# BLDC.net
KiCad netlist of a schematic drawn in EasyEDA Pro
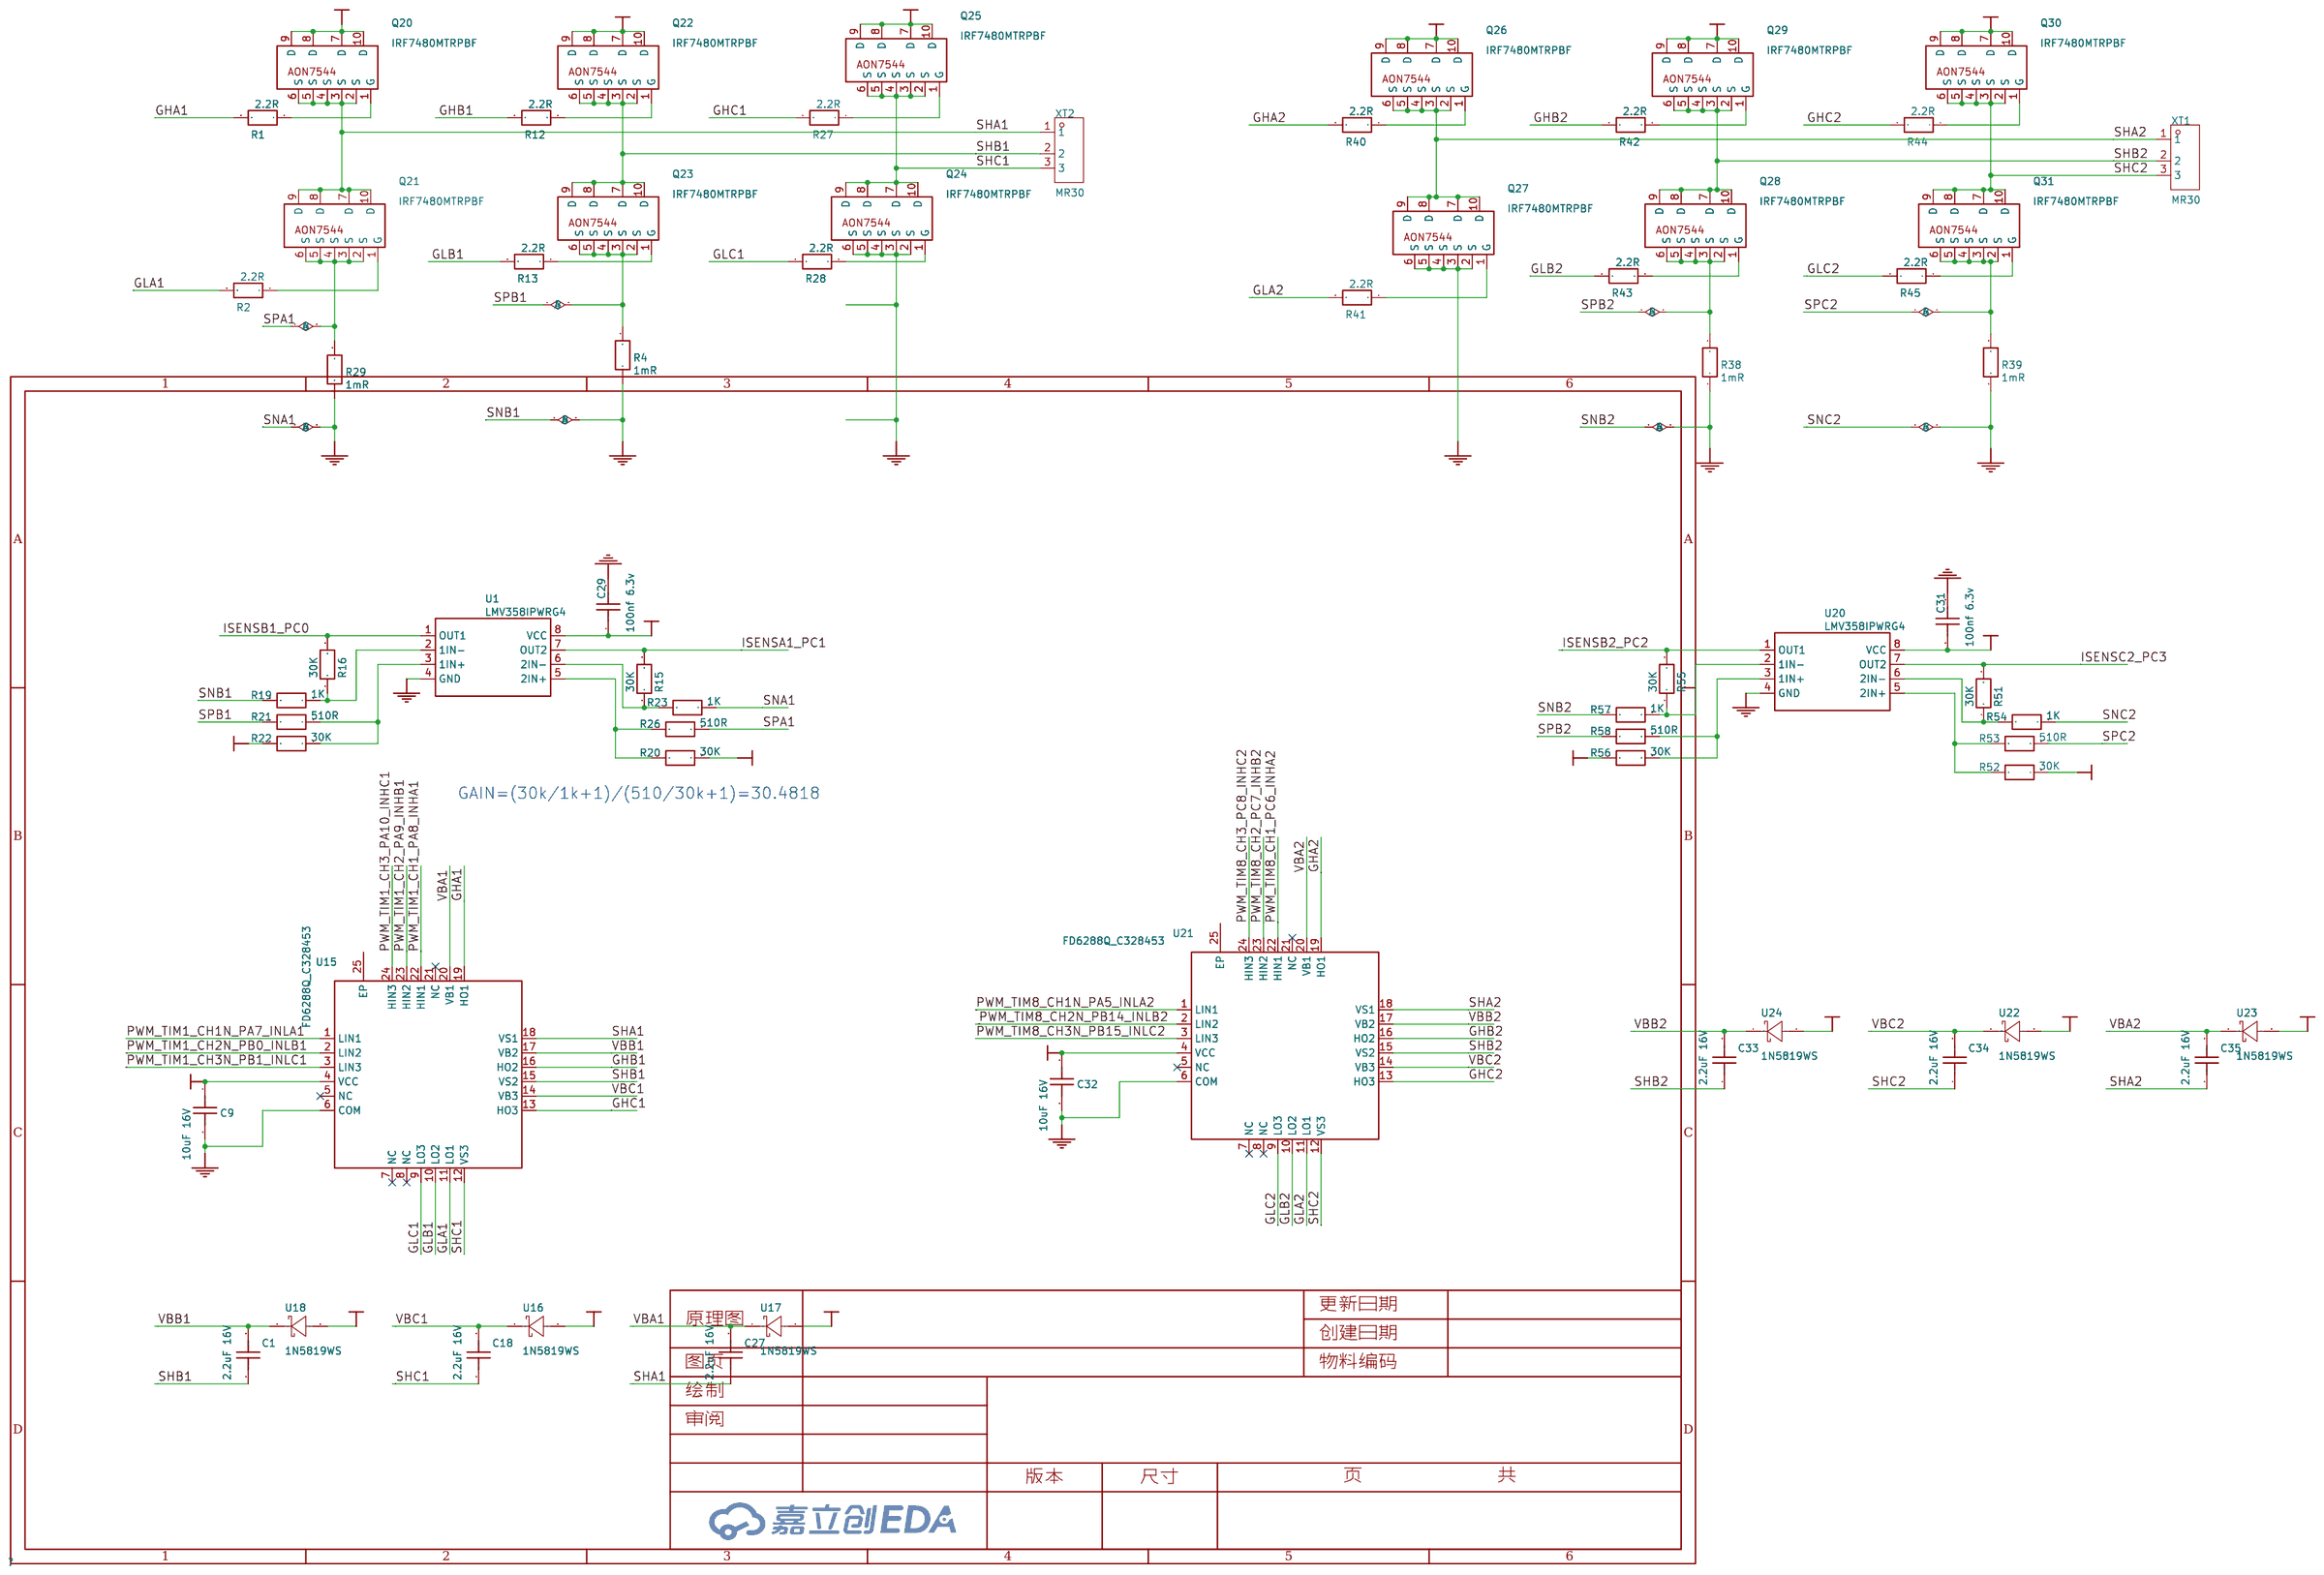
[diagram p0: 驱动]
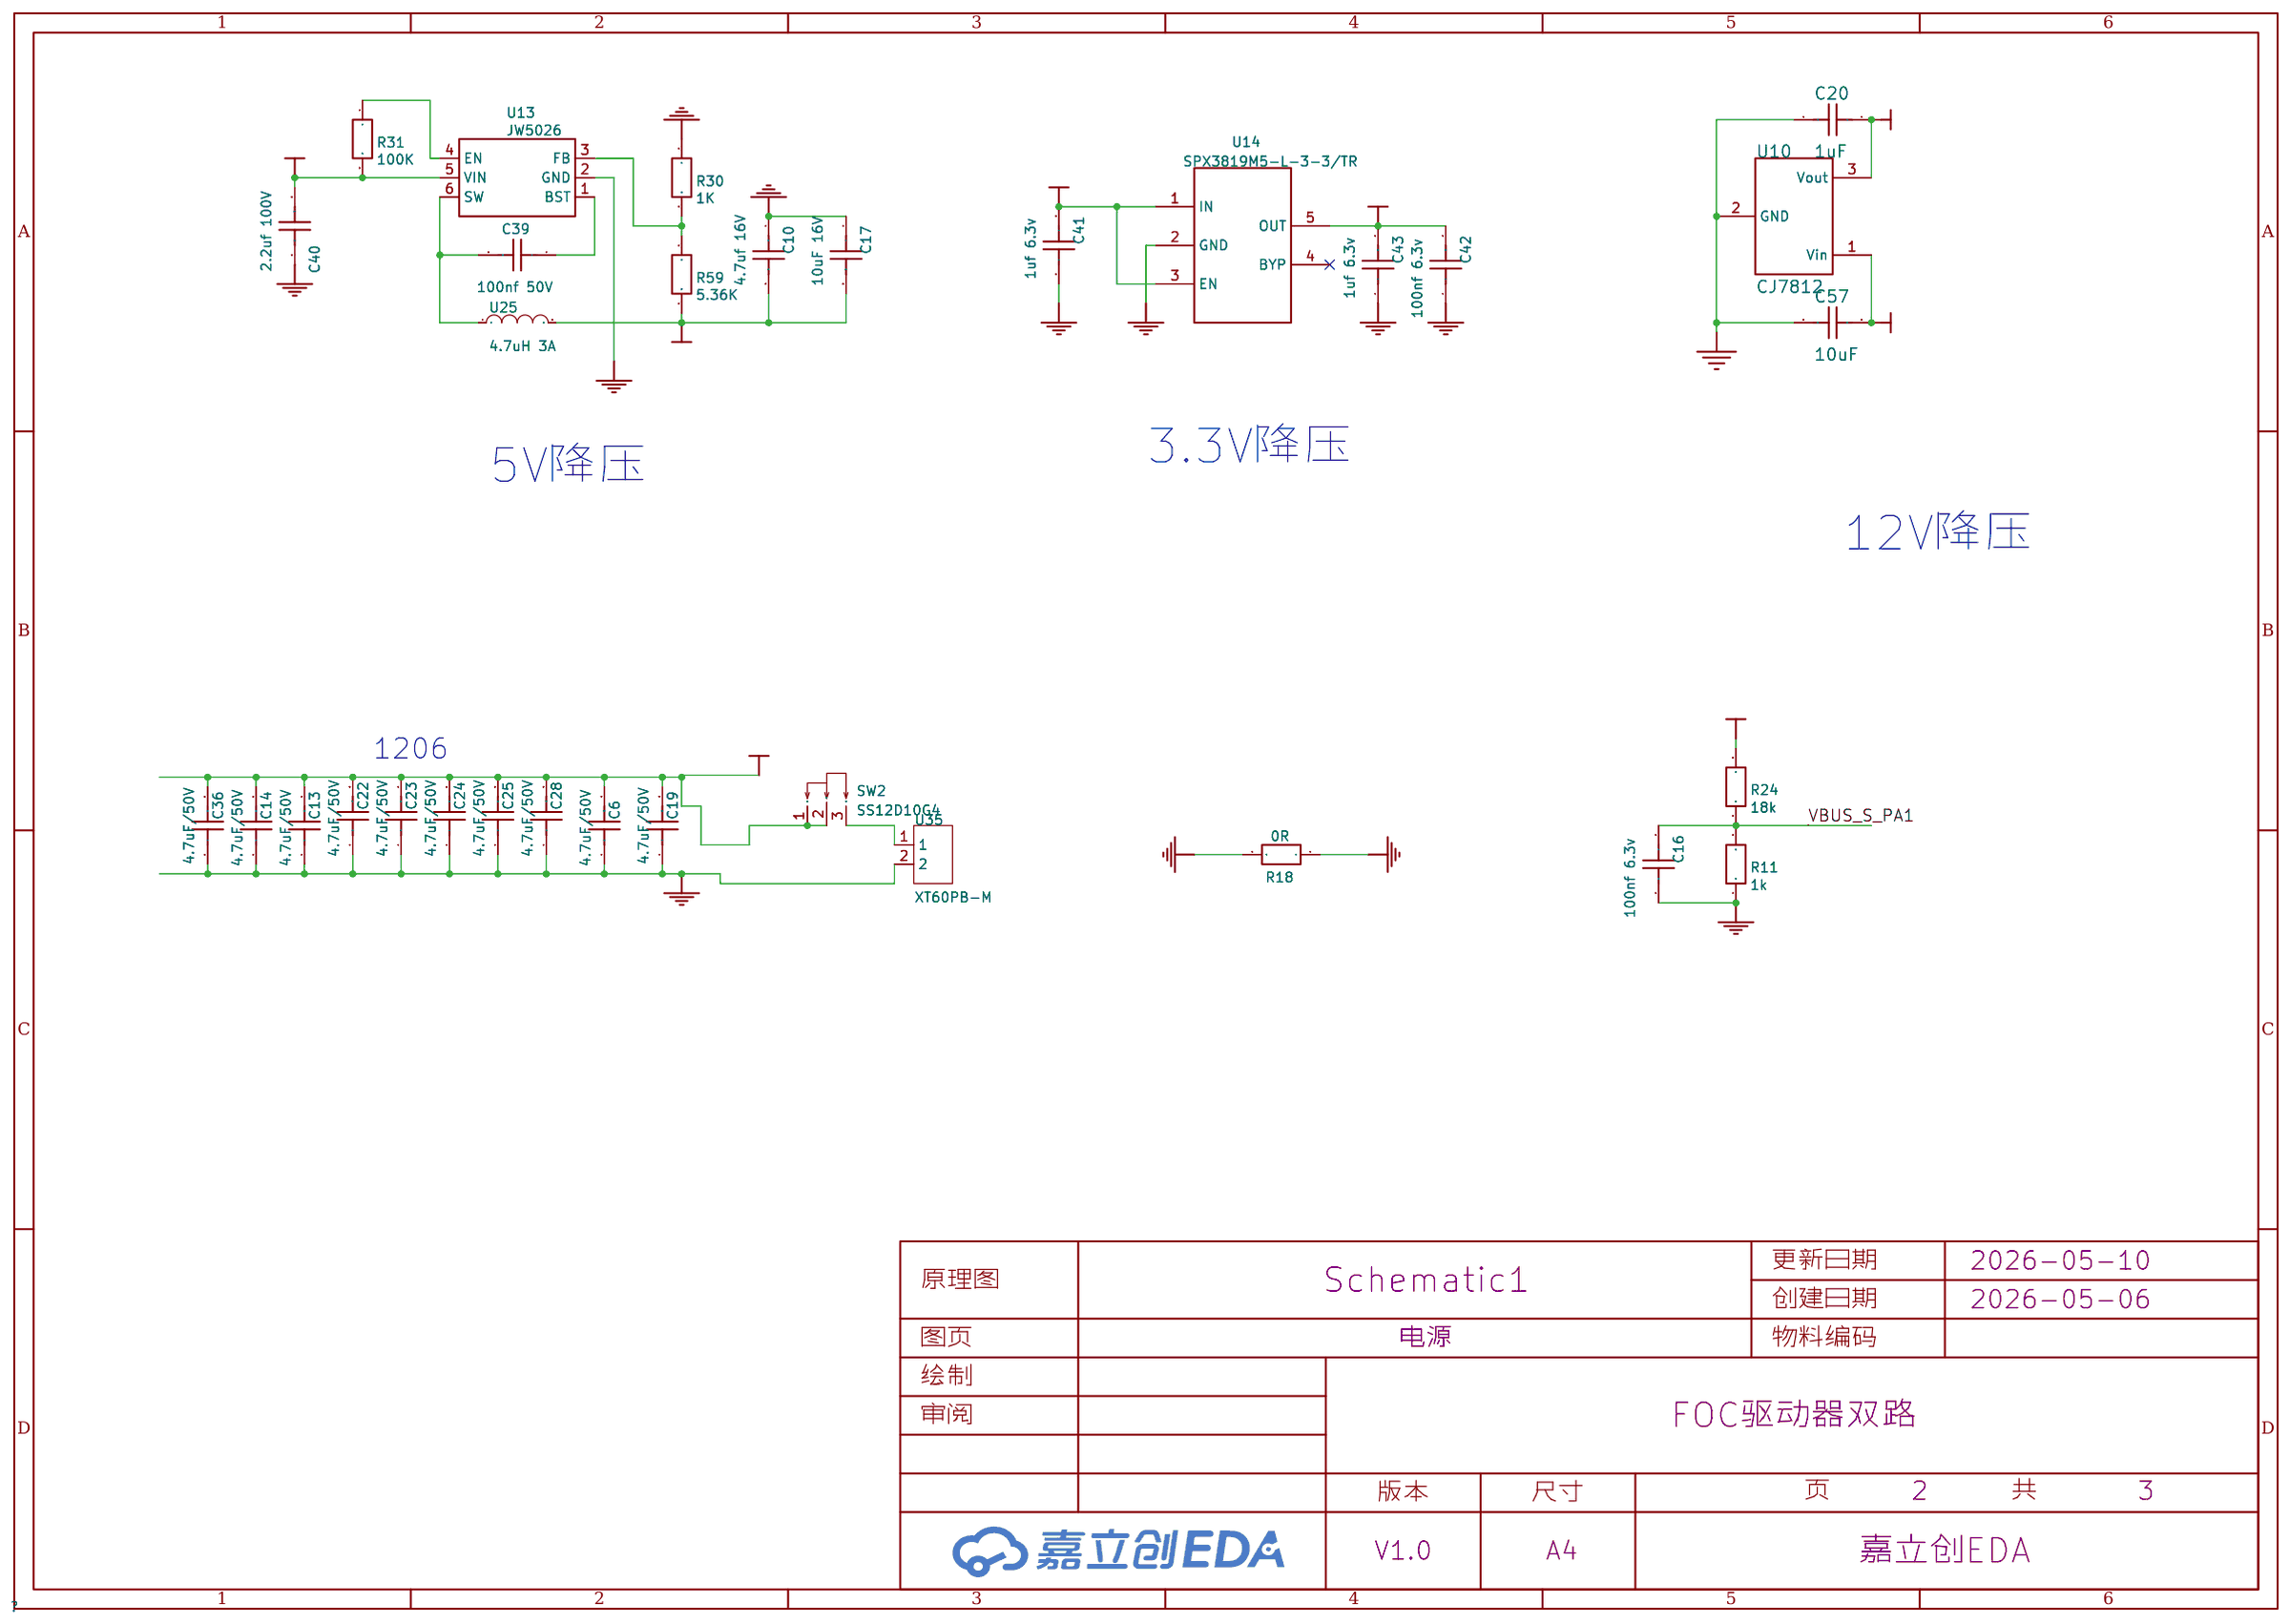
[diagram p1: 电源]
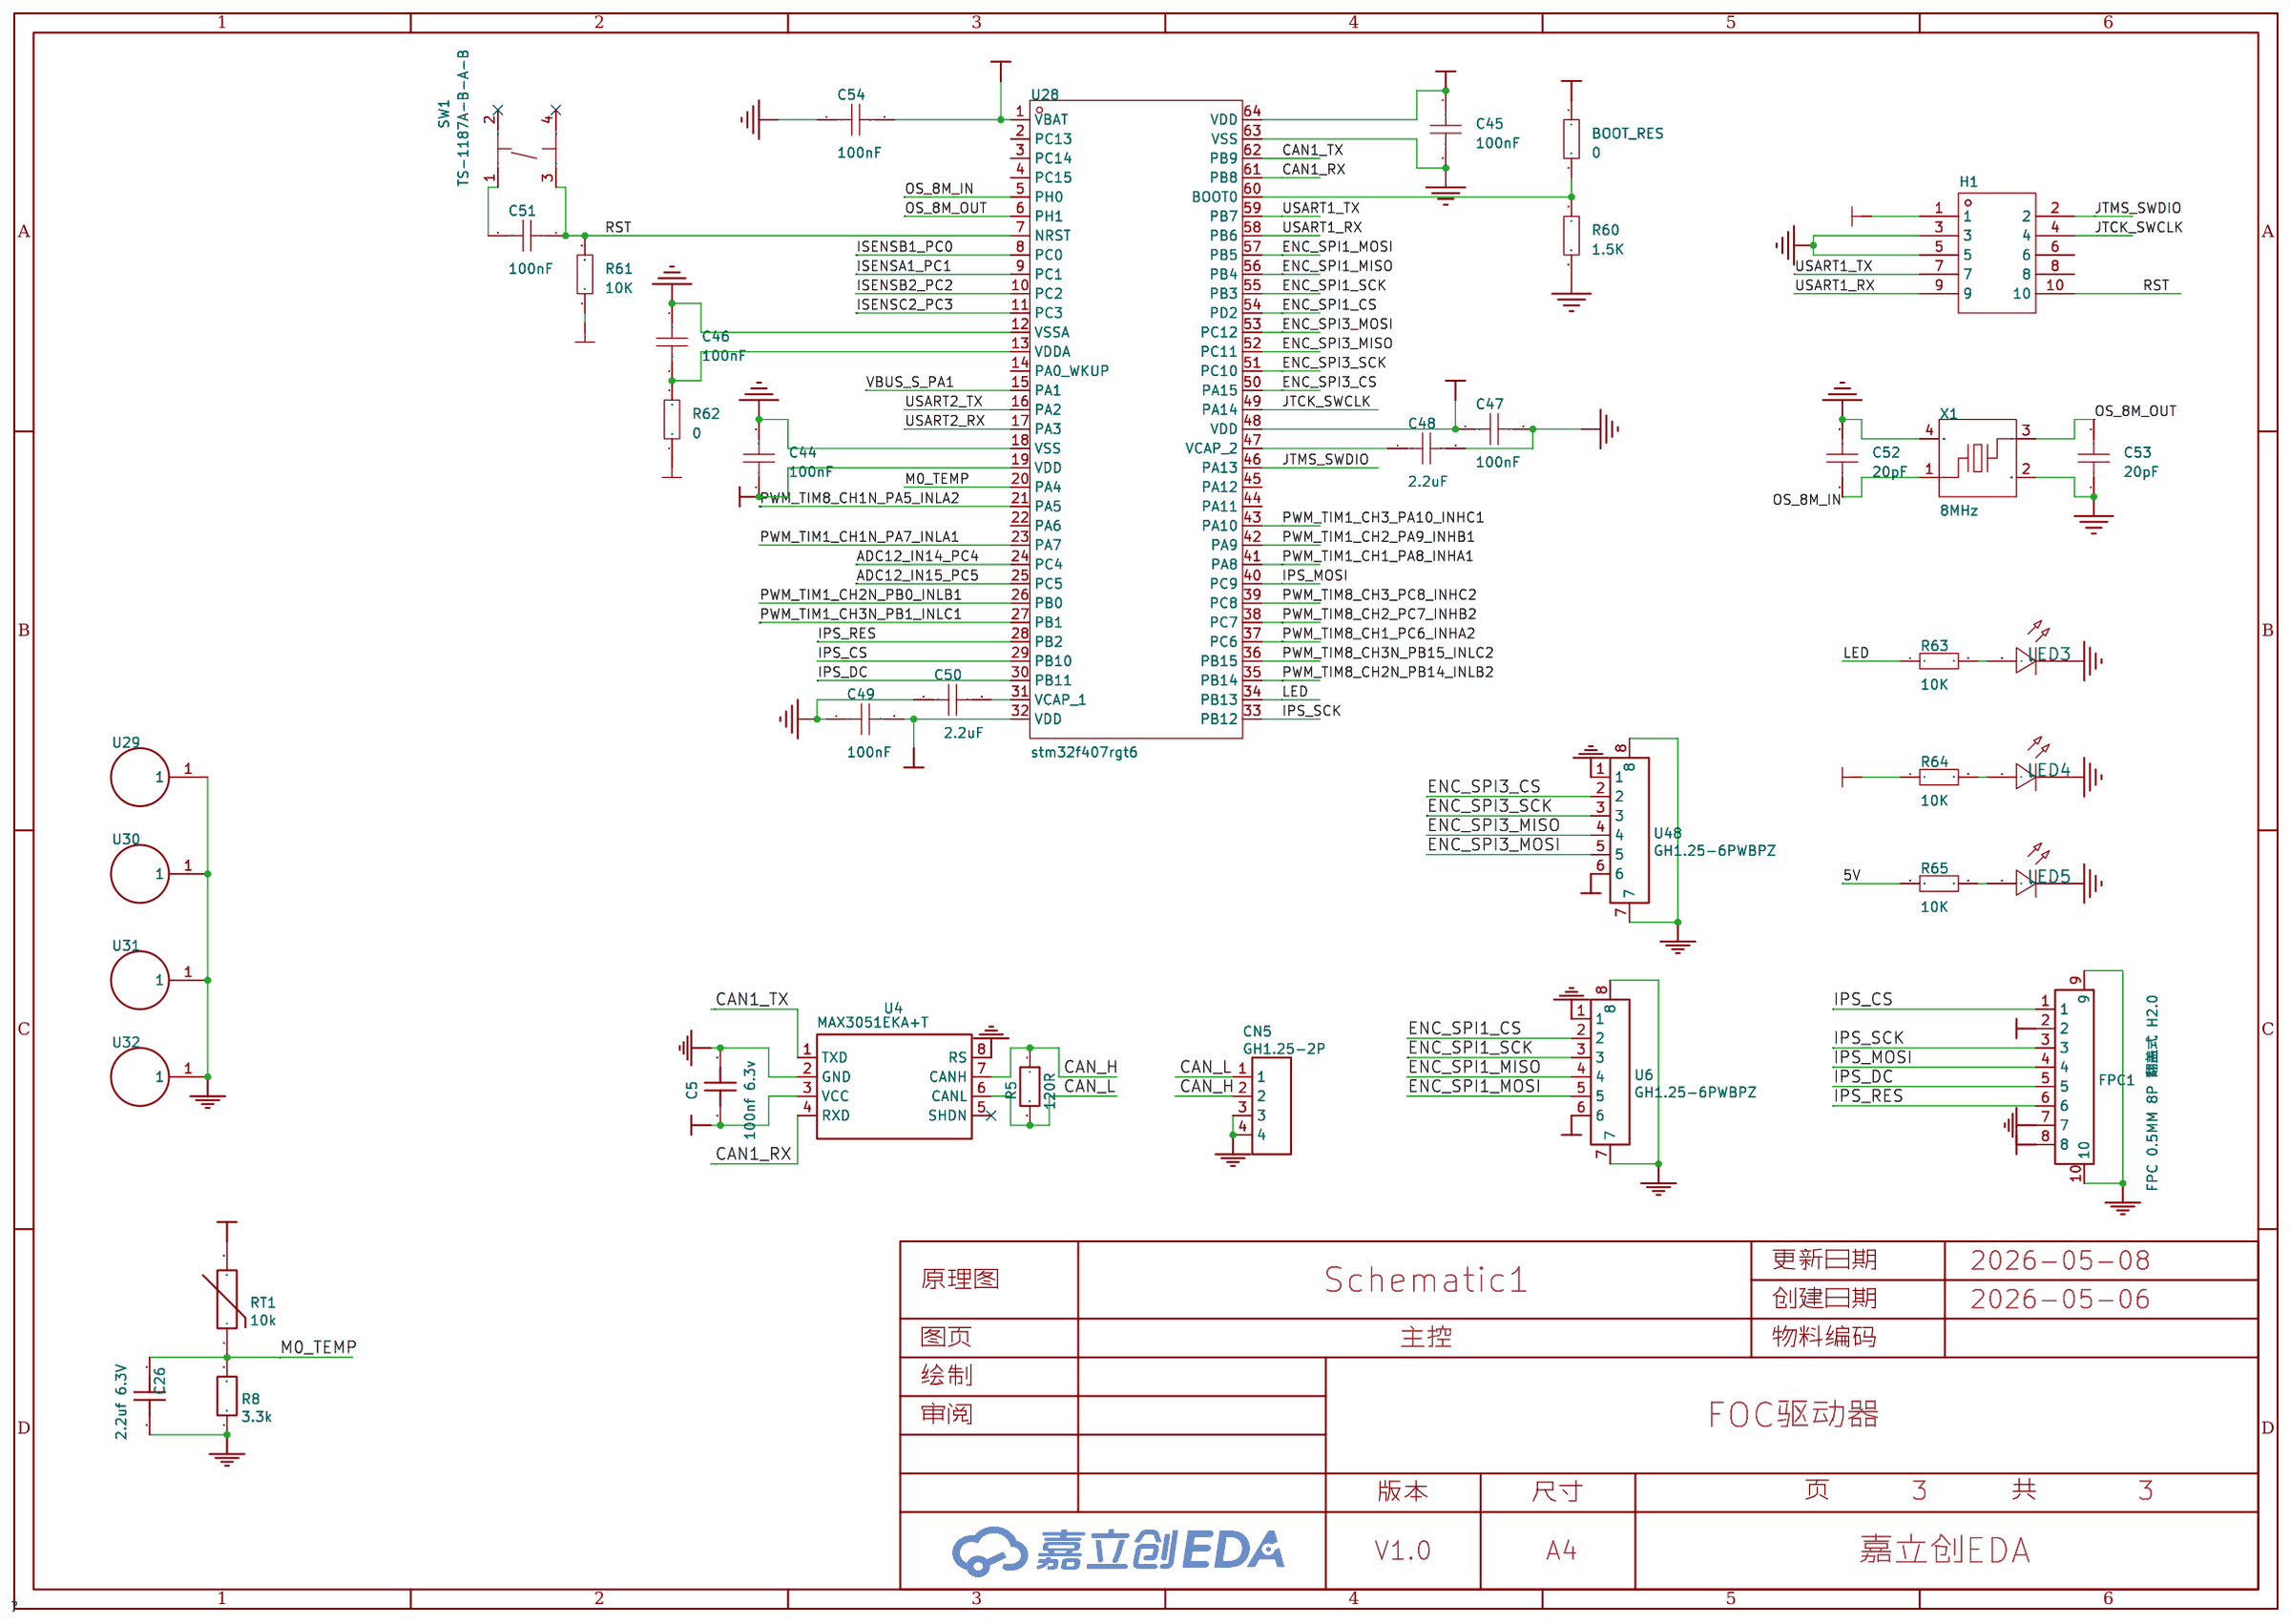
[diagram p2: 主控]

(export (version "E")
  (design (tool "Eeschema 10.0.6"))
  (components
    (comp (ref "C1")
      (value "2.2uF 16V")
      (footprint "easyedapro:C0603")
      (fields (field (name "Contributor") "LCEDA_Lib"))
      (libsource (lib "easyedapro") (part "2.2uF 16V"))
    )
    (comp (ref "C9")
      (value "10uF 16V")
      (footprint "easyedapro:C0805")
      (fields (field (name "Contributor") "LCEDA_Lib"))
      (libsource (lib "easyedapro") (part "10uF 16V"))
    )
    (comp (ref "C18")
      (value "2.2uF 16V")
      (footprint "easyedapro:C0603")
      (fields (field (name "Contributor") "LCEDA_Lib"))
      (libsource (lib "easyedapro") (part "2.2uF 16V"))
    )
    (comp (ref "C27")
      (value "2.2uF 16V")
      (footprint "easyedapro:C0603")
      (fields (field (name "Contributor") "LCEDA_Lib"))
      (libsource (lib "easyedapro") (part "2.2uF 16V"))
    )
    (comp (ref "C29")
      (value "100nf 6.3v")
      (footprint "easyedapro:C0603")
      (fields (field (name "Contributor") "LCEDA_Lib"))
      (libsource (lib "easyedapro") (part "100nf 6.3v"))
    )
    (comp (ref "C31")
      (value "100nf 6.3v")
      (footprint "easyedapro:C0603")
      (fields (field (name "Contributor") "LCEDA_Lib"))
      (libsource (lib "easyedapro") (part "100nf 6.3v"))
    )
    (comp (ref "C32")
      (value "10uF 16V")
      (footprint "easyedapro:C0805")
      (fields (field (name "Contributor") "LCEDA_Lib"))
      (libsource (lib "easyedapro") (part "10uF 16V"))
    )
    (comp (ref "C33")
      (value "2.2uF 16V")
      (footprint "easyedapro:C0603")
      (fields (field (name "Contributor") "LCEDA_Lib"))
      (libsource (lib "easyedapro") (part "2.2uF 16V"))
    )
    (comp (ref "C34")
      (value "2.2uF 16V")
      (footprint "easyedapro:C0603")
      (fields (field (name "Contributor") "LCEDA_Lib"))
      (libsource (lib "easyedapro") (part "2.2uF 16V"))
    )
    (comp (ref "C35")
      (value "2.2uF 16V")
      (footprint "easyedapro:C0603")
      (fields (field (name "Contributor") "LCEDA_Lib"))
      (libsource (lib "easyedapro") (part "2.2uF 16V"))
    )
    (comp (ref "Q20")
      (value "IRF7480MTRPBF")
      (footprint "easyedapro:TRS-SMD_IRF7480MTRPBF")
      (fields (field (name "Manufacturer") "Infineon(英飞凌)"))
      (libsource (lib "easyedapro") (part "IRF7480MTRPBF"))
    )
    (comp (ref "Q21")
      (value "IRF7480MTRPBF")
      (footprint "easyedapro:TRS-SMD_IRF7480MTRPBF")
      (fields (field (name "Manufacturer") "Infineon(英飞凌)"))
      (libsource (lib "easyedapro") (part "IRF7480MTRPBF"))
    )
    (comp (ref "Q22")
      (value "IRF7480MTRPBF")
      (footprint "easyedapro:TRS-SMD_IRF7480MTRPBF")
      (fields (field (name "Manufacturer") "Infineon(英飞凌)"))
      (libsource (lib "easyedapro") (part "IRF7480MTRPBF"))
    )
    (comp (ref "Q23")
      (value "IRF7480MTRPBF")
      (footprint "easyedapro:TRS-SMD_IRF7480MTRPBF")
      (fields (field (name "Manufacturer") "Infineon(英飞凌)"))
      (libsource (lib "easyedapro") (part "IRF7480MTRPBF"))
    )
    (comp (ref "Q24")
      (value "IRF7480MTRPBF")
      (footprint "easyedapro:TRS-SMD_IRF7480MTRPBF")
      (fields (field (name "Manufacturer") "Infineon(英飞凌)"))
      (libsource (lib "easyedapro") (part "IRF7480MTRPBF"))
    )
    (comp (ref "Q25")
      (value "IRF7480MTRPBF")
      (footprint "easyedapro:TRS-SMD_IRF7480MTRPBF")
      (fields (field (name "Manufacturer") "Infineon(英飞凌)"))
      (libsource (lib "easyedapro") (part "IRF7480MTRPBF"))
    )
    (comp (ref "Q26")
      (value "IRF7480MTRPBF")
      (footprint "easyedapro:TRS-SMD_IRF7480MTRPBF")
      (fields (field (name "Manufacturer") "Infineon(英飞凌)"))
      (libsource (lib "easyedapro") (part "IRF7480MTRPBF"))
    )
    (comp (ref "Q27")
      (value "IRF7480MTRPBF")
      (footprint "easyedapro:TRS-SMD_IRF7480MTRPBF")
      (fields (field (name "Manufacturer") "Infineon(英飞凌)"))
      (libsource (lib "easyedapro") (part "IRF7480MTRPBF"))
    )
    (comp (ref "Q28")
      (value "IRF7480MTRPBF")
      (footprint "easyedapro:TRS-SMD_IRF7480MTRPBF")
      (fields (field (name "Manufacturer") "Infineon(英飞凌)"))
      (libsource (lib "easyedapro") (part "IRF7480MTRPBF"))
    )
    (comp (ref "Q29")
      (value "IRF7480MTRPBF")
      (footprint "easyedapro:TRS-SMD_IRF7480MTRPBF")
      (fields (field (name "Manufacturer") "Infineon(英飞凌)"))
      (libsource (lib "easyedapro") (part "IRF7480MTRPBF"))
    )
    (comp (ref "Q30")
      (value "IRF7480MTRPBF")
      (footprint "easyedapro:TRS-SMD_IRF7480MTRPBF")
      (fields (field (name "Manufacturer") "Infineon(英飞凌)"))
      (libsource (lib "easyedapro") (part "IRF7480MTRPBF"))
    )
    (comp (ref "Q31")
      (value "IRF7480MTRPBF")
      (footprint "easyedapro:TRS-SMD_IRF7480MTRPBF")
      (fields (field (name "Manufacturer") "Infineon(英飞凌)"))
      (libsource (lib "easyedapro") (part "IRF7480MTRPBF"))
    )
    (comp (ref "R1")
      (value "2.2R")
      (footprint "easyedapro:R0603")
      (fields (field (name "Contributor") "LCEDA_Lib"))
      (libsource (lib "easyedapro") (part "2.2R"))
    )
    (comp (ref "R2")
      (value "2.2R")
      (footprint "easyedapro:R0603")
      (fields (field (name "Contributor") "LCEDA_Lib"))
      (libsource (lib "easyedapro") (part "2.2R"))
    )
    (comp (ref "R4")
      (value "1mR")
      (footprint "easyedapro:R1206")
      (fields (field (name "Contributor") "LCEDA_Lib"))
      (libsource (lib "easyedapro") (part "1mR"))
    )
    (comp (ref "R12")
      (value "2.2R")
      (footprint "easyedapro:R0603")
      (fields (field (name "Contributor") "LCEDA_Lib"))
      (libsource (lib "easyedapro") (part "2.2R"))
    )
    (comp (ref "R13")
      (value "2.2R")
      (footprint "easyedapro:R0603")
      (fields (field (name "Contributor") "LCEDA_Lib"))
      (libsource (lib "easyedapro") (part "2.2R"))
    )
    (comp (ref "R15")
      (value "30K")
      (footprint "easyedapro:R0603")
      (fields (field (name "Contributor") "LCEDA_Lib"))
      (libsource (lib "") (part "30K_1"))
    )
    (comp (ref "R16")
      (value "30K")
      (footprint "easyedapro:R0603")
      (fields (field (name "Contributor") "LCEDA_Lib"))
      (libsource (lib "") (part "30K_1"))
    )
    (comp (ref "R19")
      (value "1K")
      (footprint "easyedapro:R0603")
      (fields (field (name "Contributor") "LCEDA_Lib"))
      (libsource (lib "easyedapro") (part "1K"))
    )
    (comp (ref "R20")
      (value "30K")
      (footprint "easyedapro:R0603")
      (fields (field (name "Contributor") "LCEDA_Lib"))
      (libsource (lib "easyedapro") (part "30K"))
    )
    (comp (ref "R21")
      (value "510R")
      (footprint "easyedapro:R0603")
      (fields (field (name "Contributor") "LCEDA_Lib"))
      (libsource (lib "easyedapro") (part "510R"))
    )
    (comp (ref "R22")
      (value "30K")
      (footprint "easyedapro:R0603")
      (fields (field (name "Contributor") "LCEDA_Lib"))
      (libsource (lib "easyedapro") (part "30K"))
    )
    (comp (ref "R23")
      (value "1K")
      (footprint "easyedapro:R0603")
      (fields (field (name "Contributor") "LCEDA_Lib"))
      (libsource (lib "easyedapro") (part "1K"))
    )
    (comp (ref "R26")
      (value "510R")
      (footprint "easyedapro:R0603")
      (fields (field (name "Contributor") "LCEDA_Lib"))
      (libsource (lib "easyedapro") (part "510R"))
    )
    (comp (ref "R27")
      (value "2.2R")
      (footprint "easyedapro:R0603")
      (fields (field (name "Contributor") "LCEDA_Lib"))
      (libsource (lib "easyedapro") (part "2.2R"))
    )
    (comp (ref "R28")
      (value "2.2R")
      (footprint "easyedapro:R0603")
      (fields (field (name "Contributor") "LCEDA_Lib"))
      (libsource (lib "easyedapro") (part "2.2R"))
    )
    (comp (ref "R29")
      (value "1mR")
      (footprint "easyedapro:R1206")
      (fields (field (name "Contributor") "LCEDA_Lib"))
      (libsource (lib "easyedapro") (part "1mR"))
    )
    (comp (ref "R38")
      (value "1mR")
      (footprint "easyedapro:R1206")
      (fields (field (name "Contributor") "LCEDA_Lib"))
      (libsource (lib "easyedapro") (part "1mR"))
    )
    (comp (ref "R39")
      (value "1mR")
      (footprint "easyedapro:R1206")
      (fields (field (name "Contributor") "LCEDA_Lib"))
      (libsource (lib "easyedapro") (part "1mR"))
    )
    (comp (ref "R40")
      (value "2.2R")
      (footprint "easyedapro:R0603")
      (fields (field (name "Contributor") "LCEDA_Lib"))
      (libsource (lib "easyedapro") (part "2.2R"))
    )
    (comp (ref "R41")
      (value "2.2R")
      (footprint "easyedapro:R0603")
      (fields (field (name "Contributor") "LCEDA_Lib"))
      (libsource (lib "easyedapro") (part "2.2R"))
    )
    (comp (ref "R42")
      (value "2.2R")
      (footprint "easyedapro:R0603")
      (fields (field (name "Contributor") "LCEDA_Lib"))
      (libsource (lib "easyedapro") (part "2.2R"))
    )
    (comp (ref "R43")
      (value "2.2R")
      (footprint "easyedapro:R0603")
      (fields (field (name "Contributor") "LCEDA_Lib"))
      (libsource (lib "easyedapro") (part "2.2R"))
    )
    (comp (ref "R44")
      (value "2.2R")
      (footprint "easyedapro:R0603")
      (fields (field (name "Contributor") "LCEDA_Lib"))
      (libsource (lib "easyedapro") (part "2.2R"))
    )
    (comp (ref "R45")
      (value "2.2R")
      (footprint "easyedapro:R0603")
      (fields (field (name "Contributor") "LCEDA_Lib"))
      (libsource (lib "easyedapro") (part "2.2R"))
    )
    (comp (ref "R51")
      (value "30K")
      (footprint "easyedapro:R0603")
      (fields (field (name "Contributor") "LCEDA_Lib"))
      (libsource (lib "") (part "30K_1"))
    )
    (comp (ref "R52")
      (value "30K")
      (footprint "easyedapro:R0603")
      (fields (field (name "Contributor") "LCEDA_Lib"))
      (libsource (lib "easyedapro") (part "30K"))
    )
    (comp (ref "R53")
      (value "510R")
      (footprint "easyedapro:R0603")
      (fields (field (name "Contributor") "LCEDA_Lib"))
      (libsource (lib "easyedapro") (part "510R"))
    )
    (comp (ref "R54")
      (value "1K")
      (footprint "easyedapro:R0603")
      (fields (field (name "Contributor") "LCEDA_Lib"))
      (libsource (lib "easyedapro") (part "1K"))
    )
    (comp (ref "R55")
      (value "30K")
      (footprint "easyedapro:R0603")
      (fields (field (name "Contributor") "LCEDA_Lib"))
      (libsource (lib "") (part "30K_1"))
    )
    (comp (ref "R56")
      (value "30K")
      (footprint "easyedapro:R0603")
      (fields (field (name "Contributor") "LCEDA_Lib"))
      (libsource (lib "easyedapro") (part "30K"))
    )
    (comp (ref "R57")
      (value "1K")
      (footprint "easyedapro:R0603")
      (fields (field (name "Contributor") "LCEDA_Lib"))
      (libsource (lib "easyedapro") (part "1K"))
    )
    (comp (ref "R58")
      (value "510R")
      (footprint "easyedapro:R0603")
      (fields (field (name "Contributor") "LCEDA_Lib"))
      (libsource (lib "easyedapro") (part "510R"))
    )
    (comp (ref "U1")
      (value "LMV358IPWRG4")
      (footprint "easyedapro:TSSOP-8_L4.4-W3.0-P0.65-LS6.4-BL")
      (fields (field (name "Manufacturer") "TI"))
      (libsource (lib "easyedapro") (part "LMV358IPWRG4"))
    )
    (comp (ref "U15")
      (value "FD6288Q_C328453")
      (footprint "easyedapro:QFN-24_L4.0-W4.0-P0.50-BL-EP2.6")
      (fields
        (field (name "Manufacturer Part") "FD6288Q")
        (field (name "Manufacturer") "Fortior Tech")
        (field (name "Contributor") "LCSC")
      )
      (libsource (lib "easyedapro") (part "FD6288Q_C328453"))
    )
    (comp (ref "U16")
      (value "1N5819WS")
      (footprint "easyedapro:SOD-323_L1.7-W1.3-LS2.6-RD")
      (description "正向压降(Vf):600mV@1A;直流反向耐压(Vr):40V;整流电流:1A;")
      (fields (field (name "Manufacturer") "TECH PUBLIC(台舟)"))
      (libsource (lib "easyedapro") (part "1N5819WS_C7202959"))
    )
    (comp (ref "U17")
      (value "1N5819WS")
      (footprint "easyedapro:SOD-323_L1.7-W1.3-LS2.6-RD")
      (description "正向压降(Vf):600mV@1A;直流反向耐压(Vr):40V;整流电流:1A;")
      (fields (field (name "Manufacturer") "TECH PUBLIC(台舟)"))
      (libsource (lib "easyedapro") (part "1N5819WS_C7202959"))
    )
    (comp (ref "U18")
      (value "1N5819WS")
      (footprint "easyedapro:SOD-323_L1.7-W1.3-LS2.6-RD")
      (description "正向压降(Vf):600mV@1A;直流反向耐压(Vr):40V;整流电流:1A;")
      (fields (field (name "Manufacturer") "TECH PUBLIC(台舟)"))
      (libsource (lib "easyedapro") (part "1N5819WS_C7202959"))
    )
    (comp (ref "U20")
      (value "LMV358IPWRG4")
      (footprint "easyedapro:TSSOP-8_L4.4-W3.0-P0.65-LS6.4-BL")
      (fields (field (name "Manufacturer") "TI"))
      (libsource (lib "easyedapro") (part "LMV358IPWRG4"))
    )
    (comp (ref "U21")
      (value "FD6288Q_C328453")
      (footprint "easyedapro:QFN-24_L4.0-W4.0-P0.50-BL-EP2.6")
      (fields
        (field (name "Manufacturer Part") "FD6288Q")
        (field (name "Manufacturer") "Fortior Tech")
        (field (name "Contributor") "LCSC")
      )
      (libsource (lib "easyedapro") (part "FD6288Q_C328453"))
    )
    (comp (ref "U22")
      (value "1N5819WS")
      (footprint "easyedapro:SOD-323_L1.7-W1.3-LS2.6-RD")
      (description "正向压降(Vf):600mV@1A;直流反向耐压(Vr):40V;整流电流:1A;")
      (fields (field (name "Manufacturer") "TECH PUBLIC(台舟)"))
      (libsource (lib "easyedapro") (part "1N5819WS_C7202959"))
    )
    (comp (ref "U23")
      (value "1N5819WS")
      (footprint "easyedapro:SOD-323_L1.7-W1.3-LS2.6-RD")
      (description "正向压降(Vf):600mV@1A;直流反向耐压(Vr):40V;整流电流:1A;")
      (fields (field (name "Manufacturer") "TECH PUBLIC(台舟)"))
      (libsource (lib "easyedapro") (part "1N5819WS_C7202959"))
    )
    (comp (ref "U24")
      (value "1N5819WS")
      (footprint "easyedapro:SOD-323_L1.7-W1.3-LS2.6-RD")
      (description "正向压降(Vf):600mV@1A;直流反向耐压(Vr):40V;整流电流:1A;")
      (fields (field (name "Manufacturer") "TECH PUBLIC(台舟)"))
      (libsource (lib "easyedapro") (part "1N5819WS_C7202959"))
    )
    (comp (ref "U38")
      (value "~")
      (footprint "easyedapro:网络连接")
      (description "不同网络明间连接")
      (libsource (lib "easyedapro") (part "网络链接"))
    )
    (comp (ref "U39")
      (value "~")
      (footprint "easyedapro:网络连接")
      (description "不同网络明间连接")
      (libsource (lib "easyedapro") (part "网络链接"))
    )
    (comp (ref "U40")
      (value "~")
      (footprint "easyedapro:网络连接")
      (description "不同网络明间连接")
      (libsource (lib "easyedapro") (part "网络链接"))
    )
    (comp (ref "U41")
      (value "~")
      (footprint "easyedapro:网络连接")
      (description "不同网络明间连接")
      (libsource (lib "easyedapro") (part "网络链接"))
    )
    (comp (ref "U44")
      (value "~")
      (footprint "easyedapro:网络连接")
      (description "不同网络明间连接")
      (libsource (lib "easyedapro") (part "网络链接"))
    )
    (comp (ref "U45")
      (value "~")
      (footprint "easyedapro:网络连接")
      (description "不同网络明间连接")
      (libsource (lib "easyedapro") (part "网络链接"))
    )
    (comp (ref "U46")
      (value "~")
      (footprint "easyedapro:网络连接")
      (description "不同网络明间连接")
      (libsource (lib "easyedapro") (part "网络链接"))
    )
    (comp (ref "U47")
      (value "~")
      (footprint "easyedapro:网络连接")
      (description "不同网络明间连接")
      (libsource (lib "easyedapro") (part "网络链接"))
    )
    (comp (ref "XT1")
      (value "MR30")
      (footprint "easyedapro:CONN-TH_MR30PB-M")
      (libsource (lib "easyedapro") (part "MR30"))
    )
    (comp (ref "XT2")
      (value "MR30")
      (footprint "easyedapro:CONN-TH_MR30PB-M")
      (libsource (lib "easyedapro") (part "MR30"))
    )
    (comp (ref "C6")
      (value "4.7uF/50V")
      (footprint "easyedapro:C1206")
      (fields (field (name "Contributor") "LCEDA_Lib"))
      (libsource (lib "easyedapro") (part "4.7uF/50V"))
    )
    (comp (ref "C10")
      (value "4.7uf 16V")
      (footprint "easyedapro:C0603")
      (fields (field (name "Contributor") "LCEDA_Lib"))
      (libsource (lib "easyedapro") (part "4.7uf 16V"))
    )
    (comp (ref "C13")
      (value "4.7uF/50V")
      (footprint "easyedapro:C1206")
      (fields (field (name "Contributor") "LCEDA_Lib"))
      (libsource (lib "easyedapro") (part "4.7uF/50V"))
    )
    (comp (ref "C14")
      (value "4.7uF/50V")
      (footprint "easyedapro:C1206")
      (fields (field (name "Contributor") "LCEDA_Lib"))
      (libsource (lib "easyedapro") (part "4.7uF/50V"))
    )
    (comp (ref "C16")
      (value "100nf 6.3v")
      (footprint "easyedapro:C0603")
      (fields (field (name "Contributor") "LCEDA_Lib"))
      (libsource (lib "easyedapro") (part "100nf 6.3v"))
    )
    (comp (ref "C17")
      (value "10uF 16V")
      (footprint "easyedapro:C0805")
      (fields (field (name "Contributor") "LCEDA_Lib"))
      (libsource (lib "easyedapro") (part "10uF 16V"))
    )
    (comp (ref "C19")
      (value "4.7uF/50V")
      (footprint "easyedapro:C1206")
      (fields (field (name "Contributor") "LCEDA_Lib"))
      (libsource (lib "easyedapro") (part "4.7uF/50V"))
    )
    (comp (ref "C20")
      (value "1uF")
      (footprint "easyedapro:C0603")
      (libsource (lib "easyedapro") (part "CapAcitance"))
    )
    (comp (ref "C22")
      (value "4.7uF/50V")
      (footprint "easyedapro:C1206")
      (fields (field (name "Contributor") "LCEDA_Lib"))
      (libsource (lib "easyedapro") (part "4.7uF/50V"))
    )
    (comp (ref "C23")
      (value "4.7uF/50V")
      (footprint "easyedapro:C1206")
      (fields (field (name "Contributor") "LCEDA_Lib"))
      (libsource (lib "easyedapro") (part "4.7uF/50V"))
    )
    (comp (ref "C24")
      (value "4.7uF/50V")
      (footprint "easyedapro:C1206")
      (fields (field (name "Contributor") "LCEDA_Lib"))
      (libsource (lib "easyedapro") (part "4.7uF/50V"))
    )
    (comp (ref "C25")
      (value "4.7uF/50V")
      (footprint "easyedapro:C1206")
      (fields (field (name "Contributor") "LCEDA_Lib"))
      (libsource (lib "easyedapro") (part "4.7uF/50V"))
    )
    (comp (ref "C28")
      (value "4.7uF/50V")
      (footprint "easyedapro:C1206")
      (fields (field (name "Contributor") "LCEDA_Lib"))
      (libsource (lib "easyedapro") (part "4.7uF/50V"))
    )
    (comp (ref "C36")
      (value "4.7uF/50V")
      (footprint "easyedapro:C1206")
      (fields (field (name "Contributor") "LCEDA_Lib"))
      (libsource (lib "easyedapro") (part "4.7uF/50V"))
    )
    (comp (ref "C39")
      (value "100nf 50V")
      (footprint "easyedapro:C0603")
      (fields (field (name "Contributor") "LCEDA_Lib"))
      (libsource (lib "easyedapro") (part "100nf 50V"))
    )
    (comp (ref "C40")
      (value "2.2uf 100V")
      (footprint "easyedapro:C0805")
      (fields (field (name "Contributor") "LCEDA_Lib"))
      (libsource (lib "easyedapro") (part "2.2uf 100V"))
    )
    (comp (ref "C41")
      (value "1uf 6.3v")
      (footprint "easyedapro:C0603")
      (fields (field (name "Contributor") "LCEDA_Lib"))
      (libsource (lib "easyedapro") (part "1uf 6.3v"))
    )
    (comp (ref "C42")
      (value "100nf 6.3v")
      (footprint "easyedapro:C0603")
      (fields (field (name "Contributor") "LCEDA_Lib"))
      (libsource (lib "easyedapro") (part "100nf 6.3v"))
    )
    (comp (ref "C43")
      (value "1uf 6.3v")
      (footprint "easyedapro:C0603")
      (fields (field (name "Contributor") "LCEDA_Lib"))
      (libsource (lib "easyedapro") (part "1uf 6.3v"))
    )
    (comp (ref "C57")
      (value "10uF")
      (footprint "easyedapro:C0603")
      (libsource (lib "easyedapro") (part "CapAcitance"))
    )
    (comp (ref "R11")
      (value "1k")
      (footprint "easyedapro:R0603")
      (fields (field (name "Contributor") "LCEDA_Lib"))
      (libsource (lib "easyedapro") (part "1k"))
    )
    (comp (ref "R18")
      (value "0R")
      (footprint "easyedapro:R0603")
      (fields (field (name "Contributor") "LCEDA_Lib"))
      (libsource (lib "easyedapro") (part "0R"))
    )
    (comp (ref "R24")
      (value "18k")
      (footprint "easyedapro:R0603")
      (fields (field (name "Contributor") "LCEDA_Lib"))
      (libsource (lib "easyedapro") (part "18k"))
    )
    (comp (ref "R30")
      (value "1K")
      (footprint "easyedapro:R0603")
      (fields (field (name "Contributor") "LCEDA_Lib"))
      (libsource (lib "easyedapro") (part "1K"))
    )
    (comp (ref "R31")
      (value "100K")
      (footprint "easyedapro:R0603")
      (fields (field (name "Contributor") "LCEDA_Lib"))
      (libsource (lib "easyedapro") (part "100K"))
    )
    (comp (ref "R59")
      (value "5.36K")
      (footprint "easyedapro:R0603")
      (fields (field (name "Contributor") "LCEDA_Lib"))
      (libsource (lib "easyedapro") (part "5.36K"))
    )
    (comp (ref "SW2")
      (value "SS12D10G4")
      (footprint "easyedapro:SW-TH_3P-P4.80-HX-SS12D10G4")
      (fields (field (name "Manufacturer") "HanElectricity(瀚源)"))
      (libsource (lib "easyedapro") (part "SS12D10G4"))
    )
    (comp (ref "U10")
      (value "CJ7812")
      (footprint "easyedapro:TO-252-3_L6.5-W5.8-P4.58-BL")
      (fields (field (name "Manufacturer") "CJ(江苏长电/长晶)"))
      (libsource (lib "easyedapro") (part "CJ7812 3%"))
    )
    (comp (ref "U13")
      (value "JW5026")
      (footprint "easyedapro:SOT-23-6_L2.9-W1.6-P0.95-LS2.8-BR")
      (fields (field (name "Manufacturer") "JoulWatt Tech") (field (name "Contributor") "LCSC"))
      (libsource (lib "easyedapro") (part "JW5026"))
    )
    (comp (ref "U14")
      (value "SPX3819M5-L-3-3/TR")
      (footprint "easyedapro:SOT-23-5_L3.0-W1.7-P0.95-LS2.8-BR")
      (fields (field (name "Manufacturer") "EXAR"))
      (libsource (lib "easyedapro") (part "SPX3819M5-L-3-3/TR"))
    )
    (comp (ref "U25")
      (value "4.7uH 3A")
      (footprint "easyedapro:IND-SMD_L7.3-W7.3_GSDRH74P")
      (libsource (lib "easyedapro") (part "4.7UH 3A"))
    )
    (comp (ref "U35")
      (value "XT60PB-M")
      (footprint "easyedapro:CONN-TH_XT60PB-M")
      (libsource (lib "easyedapro") (part "XT60PB-M"))
    )
    (comp (ref "BOOT_RES")
      (value "0")
      (footprint "easyedapro:R0603")
      (libsource (lib "easyedapro") (part "电阻"))
    )
    (comp (ref "C5")
      (value "100nf 6.3v")
      (footprint "easyedapro:C0603")
      (fields (field (name "Contributor") "LCEDA_Lib"))
      (libsource (lib "easyedapro") (part "100nf 6.3v"))
    )
    (comp (ref "C26")
      (value "2.2uf 6.3V")
      (footprint "easyedapro:C0603")
      (fields (field (name "Contributor") "LCEDA_Lib"))
      (libsource (lib "easyedapro") (part "2.2uf 6.3V"))
    )
    (comp (ref "C44")
      (value "100nF")
      (footprint "easyedapro:C0603")
      (libsource (lib "easyedapro") (part "Capacitance"))
    )
    (comp (ref "C45")
      (value "100nF")
      (footprint "easyedapro:C0603")
      (libsource (lib "easyedapro") (part "Capacitance"))
    )
    (comp (ref "C46")
      (value "100nF")
      (footprint "easyedapro:C0603")
      (libsource (lib "easyedapro") (part "Capacitance"))
    )
    (comp (ref "C47")
      (value "100nF")
      (footprint "easyedapro:C0603")
      (libsource (lib "easyedapro") (part "Capacitance"))
    )
    (comp (ref "C48")
      (value "2.2uF")
      (footprint "easyedapro:C0603")
      (libsource (lib "easyedapro") (part "Capacitance"))
    )
    (comp (ref "C49")
      (value "100nF")
      (footprint "easyedapro:C0603")
      (libsource (lib "easyedapro") (part "Capacitance"))
    )
    (comp (ref "C50")
      (value "2.2uF")
      (footprint "easyedapro:C0603")
      (libsource (lib "easyedapro") (part "Capacitance"))
    )
    (comp (ref "C51")
      (value "100nF")
      (footprint "easyedapro:C0603")
      (libsource (lib "easyedapro") (part "Capacitance"))
    )
    (comp (ref "C52")
      (value "20pF")
      (footprint "easyedapro:C0603")
      (libsource (lib "easyedapro") (part "Capacitance"))
    )
    (comp (ref "C53")
      (value "20pF")
      (footprint "easyedapro:C0603")
      (libsource (lib "easyedapro") (part "Capacitance"))
    )
    (comp (ref "C54")
      (value "100nF")
      (footprint "easyedapro:C0603")
      (libsource (lib "easyedapro") (part "Capacitance"))
    )
    (comp (ref "CN5")
      (value "GH1.25-2P")
      (footprint "easyedapro:CONN-SMD_2P-P1.25_GH1.25-2P")
      (fields (field (name "Contributor") "LCSC"))
      (libsource (lib "easyedapro") (part "GH1.25-2P"))
    )
    (comp (ref "FPC1")
      (value "FPC 0.5MM 8P 翻盖式 H2.0")
      (footprint "easyedapro:FPC-SMD_FPC-0.5MM-8P")
      (fields (field (name "Manufacturer") "ATOM(爱特姆)") (field (name "Contributor") "LCSC"))
      (libsource (lib "easyedapro") (part "FPC 0.5MM 8P 翻盖式 H2.0"))
    )
    (comp (ref "H1")
      (value "~")
      (footprint "easyedapro:HDR-TH_10P-P2.54-V-M-R2-C5-S2.54")
      (libsource (lib "easyedapro") (part "HDR-M-2.54_2x5"))
    )
    (comp (ref "LED3")
      (value "~")
      (footprint "easyedapro:LED_0603")
      (libsource (lib "easyedapro") (part "LED_R"))
    )
    (comp (ref "LED4")
      (value "~")
      (footprint "easyedapro:LED_0603")
      (libsource (lib "easyedapro") (part "LED_R"))
    )
    (comp (ref "LED5")
      (value "~")
      (footprint "easyedapro:LED_0603")
      (libsource (lib "easyedapro") (part "LED_R"))
    )
    (comp (ref "R5")
      (value "120R")
      (footprint "easyedapro:R0603")
      (fields (field (name "Contributor") "LCEDA_Lib"))
      (libsource (lib "easyedapro") (part "120R"))
    )
    (comp (ref "R8")
      (value "3.3k")
      (footprint "easyedapro:R0603")
      (fields (field (name "Contributor") "LCEDA_Lib"))
      (libsource (lib "easyedapro") (part "3.3k"))
    )
    (comp (ref "R60")
      (value "1.5K")
      (footprint "easyedapro:R0603")
      (libsource (lib "easyedapro") (part "电阻"))
    )
    (comp (ref "R61") (value "10K") (footprint "easyedapro:R0603") (libsource (lib "easyedapro") (part "电阻")))
    (comp (ref "R62") (value "0") (footprint "easyedapro:R0603") (libsource (lib "easyedapro") (part "电阻")))
    (comp (ref "R63") (value "10K") (footprint "easyedapro:R0603") (libsource (lib "easyedapro") (part "电阻")))
    (comp (ref "R64") (value "10K") (footprint "easyedapro:R0603") (libsource (lib "easyedapro") (part "电阻")))
    (comp (ref "R65") (value "10K") (footprint "easyedapro:R0603") (libsource (lib "easyedapro") (part "电阻")))
    (comp (ref "RT1")
      (value "10k")
      (footprint "easyedapro:R0603")
      (fields
        (field (name "Manufacturer Part") "NTCG164BH103JT1")
        (field (name "Manufacturer") "TDK")
        (field (name "Contributor") "LCSC")
      )
      (libsource (lib "easyedapro") (part "10k"))
    )
    (comp (ref "SW1")
      (value "TS-1187A-B-A-B")
      (footprint "easyedapro:SW-SMD_4P-L5.1-W5.1-P3.70-LS6.5-TL_H1.5")
      (fields (field (name "Manufacturer") "XKB Connection(中国星坤)"))
      (libsource (lib "easyedapro") (part "TS-1187A-B-A-B"))
    )
    (comp (ref "U4")
      (value "MAX3051EKA+T")
      (footprint "easyedapro:SOT-23-8_L3.0-W1.7-P0.65-LS2.8-TL")
      (fields (field (name "Manufacturer") "MAXIM"))
      (libsource (lib "easyedapro") (part "MAX3051EKA+T"))
    )
    (comp (ref "U6")
      (value "GH1.25-6PWBPZ")
      (footprint "easyedapro:CONN-SMD_6P-P1.25_GH1.25-6PWBPZ")
      (fields (field (name "Manufacturer") "BOOMELE(博穆精密)") (field (name "Contributor") "LCSC"))
      (libsource (lib "easyedapro") (part "GH1.25-6PWBPZ"))
    )
    (comp (ref "U28")
      (value "stm32f407rgt6")
      (footprint "easyedapro:LQFP-64_L10.0-W10.0-P0.50-LS12.0-BL")
      (libsource (lib "easyedapro") (part "STM32F407RGT6"))
    )
    (comp (ref "U29")
      (value "~")
      (footprint "easyedapro:M3")
      (description "M3定位孔")
      (libsource (lib "easyedapro") (part "M3"))
    )
    (comp (ref "U30")
      (value "~")
      (footprint "easyedapro:M3")
      (description "M3定位孔")
      (libsource (lib "easyedapro") (part "M3"))
    )
    (comp (ref "U31")
      (value "~")
      (footprint "easyedapro:M3")
      (description "M3定位孔")
      (libsource (lib "easyedapro") (part "M3"))
    )
    (comp (ref "U32")
      (value "~")
      (footprint "easyedapro:M3")
      (description "M3定位孔")
      (libsource (lib "easyedapro") (part "M3"))
    )
    (comp (ref "U48")
      (value "GH1.25-6PWBPZ")
      (footprint "easyedapro:CONN-SMD_6P-P1.25_GH1.25-6PWBPZ")
      (fields (field (name "Manufacturer") "BOOMELE(博穆精密)") (field (name "Contributor") "LCSC"))
      (libsource (lib "easyedapro") (part "GH1.25-6PWBPZ"))
    )
    (comp (ref "X1")
      (value "8MHz")
      (footprint "easyedapro:CRYSTAL-SMD_4P-L3.2-W2.5-BL-1")
      (description "晶振类型:贴片晶振;频率:8MHz;常温频差:±10ppm;负载电容:12pF;频率稳定度:±20ppm;")
      (fields
        (field (name "Manufacturer Part") "XL2EL89COI-111YLC-8M")
        (field (name "Manufacturer") "YXC(扬兴晶振)")
      )
      (libsource (lib "easyedapro") (part "XL2EL89COI-111YLC-8M"))
    )
  )
  (nets
    (net (code "1") (name "5V") (class "Default")
      (node (ref "C10") (pin "2") (pinfunction "2_2") (pintype "unspecified"))
      (node (ref "C17") (pin "2") (pinfunction "2_2") (pintype "unspecified"))
      (node (ref "C41") (pin "2") (pinfunction "2_2") (pintype "unspecified"))
      (node (ref "R59") (pin "2") (pinfunction "2_2") (pintype "unspecified"))
      (node (ref "R65") (pin "1") (pinfunction "1_1") (pintype "input"))
      (node (ref "U14") (pin "1") (pinfunction "IN_1") (pintype "unspecified"))
      (node (ref "U14") (pin "3") (pinfunction "EN_3") (pintype "unspecified"))
      (node (ref "U25") (pin "2") (pinfunction "2_2") (pintype "unspecified"))
    )
    (net (code "2") (name "12V") (class "Default")
      (node (ref "C20") (pin "1") (pinfunction "1_1") (pintype "input"))
      (node (ref "C32") (pin "1") (pinfunction "1_1") (pintype "unspecified"))
      (node (ref "C9") (pin "1") (pinfunction "1_1") (pintype "unspecified"))
      (node (ref "U10") (pin "3") (pinfunction "Vout_3") (pintype "unspecified"))
      (node (ref "U15") (pin "4") (pinfunction "VCC_4") (pintype "unspecified"))
      (node (ref "U16") (pin "2") (pinfunction "A_2") (pintype "unspecified"))
      (node (ref "U17") (pin "2") (pinfunction "A_2") (pintype "unspecified"))
      (node (ref "U18") (pin "2") (pinfunction "A_2") (pintype "unspecified"))
      (node (ref "U21") (pin "4") (pinfunction "VCC_4") (pintype "unspecified"))
      (node (ref "U22") (pin "2") (pinfunction "A_2") (pintype "unspecified"))
      (node (ref "U23") (pin "2") (pinfunction "A_2") (pintype "unspecified"))
      (node (ref "U24") (pin "2") (pinfunction "A_2") (pintype "unspecified"))
    )
    (net (code "3") (name "ADC12_IN14_PC4") (class "Default")
      (node (ref "U28") (pin "24") (pinfunction "PC4_24") (pintype "unspecified"))
    )
    (net (code "4") (name "ADC12_IN15_PC5") (class "Default")
      (node (ref "U28") (pin "25") (pinfunction "PC5_25") (pintype "unspecified"))
    )
    (net (code "5") (name "CAN1_RX") (class "Default")
      (node (ref "U28") (pin "61") (pinfunction "PB8_61") (pintype "unspecified"))
      (node (ref "U4") (pin "4") (pinfunction "RXD_4") (pintype "unspecified"))
    )
    (net (code "6") (name "CAN1_TX") (class "Default")
      (node (ref "U28") (pin "62") (pinfunction "PB9_62") (pintype "unspecified"))
      (node (ref "U4") (pin "1") (pinfunction "TXD_1") (pintype "unspecified"))
    )
    (net (code "7") (name "CAN_H") (class "Default")
      (node (ref "CN5") (pin "2") (pinfunction "2_2") (pintype "unspecified"))
      (node (ref "R5") (pin "1") (pinfunction "1_1") (pintype "unspecified"))
      (node (ref "U4") (pin "7") (pinfunction "CANH_7") (pintype "unspecified"))
    )
    (net (code "8") (name "CAN_L") (class "Default")
      (node (ref "CN5") (pin "1") (pinfunction "1_1") (pintype "unspecified"))
      (node (ref "R5") (pin "2") (pinfunction "2_2") (pintype "unspecified"))
      (node (ref "U4") (pin "6") (pinfunction "CANL_6") (pintype "unspecified"))
    )
    (net (code "9") (name "DCBUS") (class "Default")
      (node (ref "C13") (pin "2") (pinfunction "2_2") (pintype "unspecified"))
      (node (ref "C14") (pin "2") (pinfunction "2_2") (pintype "unspecified"))
      (node (ref "C19") (pin "2") (pinfunction "2_2") (pintype "unspecified"))
      (node (ref "C22") (pin "2") (pinfunction "2_2") (pintype "unspecified"))
      (node (ref "C23") (pin "2") (pinfunction "2_2") (pintype "unspecified"))
      (node (ref "C24") (pin "2") (pinfunction "2_2") (pintype "unspecified"))
      (node (ref "C25") (pin "2") (pinfunction "2_2") (pintype "unspecified"))
      (node (ref "C28") (pin "2") (pinfunction "2_2") (pintype "unspecified"))
      (node (ref "C36") (pin "2") (pinfunction "2_2") (pintype "unspecified"))
      (node (ref "C40") (pin "2") (pinfunction "2_2") (pintype "unspecified"))
      (node (ref "C57") (pin "1") (pinfunction "1_1") (pintype "input"))
      (node (ref "C6") (pin "2") (pinfunction "2_2") (pintype "unspecified"))
      (node (ref "Q20") (pin "10") (pinfunction "D_10") (pintype "unspecified"))
      (node (ref "Q20") (pin "7") (pinfunction "D_7") (pintype "unspecified"))
      (node (ref "Q20") (pin "8") (pinfunction "D_8") (pintype "unspecified"))
      (node (ref "Q20") (pin "9") (pinfunction "D_9") (pintype "unspecified"))
      (node (ref "Q22") (pin "10") (pinfunction "D_10") (pintype "unspecified"))
      (node (ref "Q22") (pin "7") (pinfunction "D_7") (pintype "unspecified"))
      (node (ref "Q22") (pin "8") (pinfunction "D_8") (pintype "unspecified"))
      (node (ref "Q22") (pin "9") (pinfunction "D_9") (pintype "unspecified"))
      (node (ref "Q25") (pin "10") (pinfunction "D_10") (pintype "unspecified"))
      (node (ref "Q25") (pin "7") (pinfunction "D_7") (pintype "unspecified"))
      (node (ref "Q25") (pin "8") (pinfunction "D_8") (pintype "unspecified"))
      (node (ref "Q25") (pin "9") (pinfunction "D_9") (pintype "unspecified"))
      (node (ref "Q26") (pin "10") (pinfunction "D_10") (pintype "unspecified"))
      (node (ref "Q26") (pin "7") (pinfunction "D_7") (pintype "unspecified"))
      (node (ref "Q26") (pin "8") (pinfunction "D_8") (pintype "unspecified"))
      (node (ref "Q26") (pin "9") (pinfunction "D_9") (pintype "unspecified"))
      (node (ref "Q29") (pin "10") (pinfunction "D_10") (pintype "unspecified"))
      (node (ref "Q29") (pin "7") (pinfunction "D_7") (pintype "unspecified"))
      (node (ref "Q29") (pin "8") (pinfunction "D_8") (pintype "unspecified"))
      (node (ref "Q29") (pin "9") (pinfunction "D_9") (pintype "unspecified"))
      (node (ref "Q30") (pin "10") (pinfunction "D_10") (pintype "unspecified"))
      (node (ref "Q30") (pin "7") (pinfunction "D_7") (pintype "unspecified"))
      (node (ref "Q30") (pin "8") (pinfunction "D_8") (pintype "unspecified"))
      (node (ref "Q30") (pin "9") (pinfunction "D_9") (pintype "unspecified"))
      (node (ref "R24") (pin "2") (pinfunction "2_2") (pintype "unspecified"))
      (node (ref "R31") (pin "2") (pinfunction "2_2") (pintype "unspecified"))
      (node (ref "SW2") (pin "1") (pinfunction "1_1") (pintype "unspecified"))
      (node (ref "SW2") (pin "2") (pinfunction "2_2") (pintype "unspecified"))
      (node (ref "U10") (pin "1") (pinfunction "Vin_1") (pintype "unspecified"))
      (node (ref "U13") (pin "5") (pinfunction "VIN_5") (pintype "unspecified"))
    )
    (net (code "10") (name "DGND") (class "Default")
      (node (ref "C10") (pin "1") (pinfunction "1_1") (pintype "unspecified"))
      (node (ref "C16") (pin "1") (pinfunction "1_1") (pintype "unspecified"))
      (node (ref "C17") (pin "1") (pinfunction "1_1") (pintype "unspecified"))
      (node (ref "C20") (pin "2") (pinfunction "2_2") (pintype "input"))
      (node (ref "C26") (pin "2") (pinfunction "2_2") (pintype "unspecified"))
      (node (ref "C29") (pin "2") (pinfunction "2_2") (pintype "unspecified"))
      (node (ref "C31") (pin "2") (pinfunction "2_2") (pintype "unspecified"))
      (node (ref "C32") (pin "2") (pinfunction "2_2") (pintype "unspecified"))
      (node (ref "C40") (pin "1") (pinfunction "1_1") (pintype "unspecified"))
      (node (ref "C41") (pin "1") (pinfunction "1_1") (pintype "unspecified"))
      (node (ref "C42") (pin "1") (pinfunction "1_1") (pintype "unspecified"))
      (node (ref "C43") (pin "1") (pinfunction "1_1") (pintype "unspecified"))
      (node (ref "C44") (pin "2") (pinfunction "2_2") (pintype "input"))
      (node (ref "C45") (pin "2") (pinfunction "2_2") (pintype "input"))
      (node (ref "C46") (pin "2") (pinfunction "2_2") (pintype "input"))
      (node (ref "C47") (pin "2") (pinfunction "2_2") (pintype "input"))
      (node (ref "C48") (pin "2") (pinfunction "2_2") (pintype "input"))
      (node (ref "C49") (pin "1") (pinfunction "1_1") (pintype "input"))
      (node (ref "C5") (pin "2") (pinfunction "2_2") (pintype "unspecified"))
      (node (ref "C50") (pin "1") (pinfunction "1_1") (pintype "input"))
      (node (ref "C52") (pin "2") (pinfunction "2_2") (pintype "input"))
      (node (ref "C53") (pin "1") (pinfunction "1_1") (pintype "input"))
      (node (ref "C54") (pin "1") (pinfunction "1_1") (pintype "input"))
      (node (ref "C57") (pin "2") (pinfunction "2_2") (pintype "input"))
      (node (ref "C9") (pin "2") (pinfunction "2_2") (pintype "unspecified"))
      (node (ref "CN5") (pin "3") (pinfunction "3_3") (pintype "unspecified"))
      (node (ref "CN5") (pin "4") (pinfunction "4_4") (pintype "unspecified"))
      (node (ref "FPC1") (pin "10") (pinfunction "10_10") (pintype "unspecified"))
      (node (ref "FPC1") (pin "7") (pinfunction "7_7") (pintype "unspecified"))
      (node (ref "FPC1") (pin "9") (pinfunction "9_9") (pintype "unspecified"))
      (node (ref "H1") (pin "3") (pinfunction "3_3") (pintype "input"))
      (node (ref "H1") (pin "5") (pinfunction "5_5") (pintype "input"))
      (node (ref "LED3") (pin "1") (pinfunction "C_1") (pintype "input"))
      (node (ref "LED4") (pin "1") (pinfunction "C_1") (pintype "input"))
      (node (ref "LED5") (pin "1") (pinfunction "C_1") (pintype "input"))
      (node (ref "R11") (pin "1") (pinfunction "1_1") (pintype "unspecified"))
      (node (ref "R18") (pin "2") (pinfunction "2_2") (pintype "unspecified"))
      (node (ref "R30") (pin "1") (pinfunction "1_1") (pintype "unspecified"))
      (node (ref "R60") (pin "2") (pinfunction "2_2") (pintype "input"))
      (node (ref "R8") (pin "1") (pinfunction "1_1") (pintype "unspecified"))
      (node (ref "U1") (pin "4") (pinfunction "GND_4") (pintype "unspecified"))
      (node (ref "U10") (pin "2") (pinfunction "GND_2") (pintype "unspecified"))
      (node (ref "U13") (pin "2") (pinfunction "GND_2") (pintype "unspecified"))
      (node (ref "U14") (pin "2") (pinfunction "GND_2") (pintype "unspecified"))
      (node (ref "U15") (pin "6") (pinfunction "COM_6") (pintype "unspecified"))
      (node (ref "U20") (pin "4") (pinfunction "GND_4") (pintype "unspecified"))
      (node (ref "U21") (pin "6") (pinfunction "COM_6") (pintype "unspecified"))
      (node (ref "U28") (pin "12") (pinfunction "VSSA_12") (pintype "unspecified"))
      (node (ref "U28") (pin "18") (pinfunction "VSS_18") (pintype "unspecified"))
      (node (ref "U28") (pin "63") (pinfunction "VSS_63") (pintype "unspecified"))
      (node (ref "U29") (pin "1") (pinfunction "1_1") (pintype "input"))
      (node (ref "U30") (pin "1") (pinfunction "1_1") (pintype "input"))
      (node (ref "U31") (pin "1") (pinfunction "1_1") (pintype "input"))
      (node (ref "U32") (pin "1") (pinfunction "1_1") (pintype "input"))
      (node (ref "U4") (pin "2") (pinfunction "GND_2") (pintype "unspecified"))
      (node (ref "U4") (pin "8") (pinfunction "RS_8") (pintype "unspecified"))
      (node (ref "U48") (pin "1") (pinfunction "1_1") (pintype "unspecified"))
      (node (ref "U48") (pin "7") (pinfunction "7_7") (pintype "unspecified"))
      (node (ref "U48") (pin "8") (pinfunction "8_8") (pintype "unspecified"))
      (node (ref "U6") (pin "1") (pinfunction "1_1") (pintype "unspecified"))
      (node (ref "U6") (pin "7") (pinfunction "7_7") (pintype "unspecified"))
      (node (ref "U6") (pin "8") (pinfunction "8_8") (pintype "unspecified"))
      (node (ref "X1") (pin "2") (pinfunction "GND_2") (pintype "input"))
      (node (ref "X1") (pin "4") (pinfunction "GND_4") (pintype "input"))
    )
    (net (code "11") (name "ENC_SPI1_CS") (class "Default")
      (node (ref "U28") (pin "54") (pinfunction "PD2_54") (pintype "unspecified"))
      (node (ref "U6") (pin "2") (pinfunction "2_2") (pintype "unspecified"))
    )
    (net (code "12") (name "ENC_SPI1_MISO") (class "Default")
      (node (ref "U28") (pin "56") (pinfunction "PB4_56") (pintype "unspecified"))
      (node (ref "U6") (pin "4") (pinfunction "4_4") (pintype "unspecified"))
    )
    (net (code "13") (name "ENC_SPI1_MOSI") (class "Default")
      (node (ref "U28") (pin "57") (pinfunction "PB5_57") (pintype "unspecified"))
      (node (ref "U6") (pin "5") (pinfunction "5_5") (pintype "unspecified"))
    )
    (net (code "14") (name "ENC_SPI1_SCK") (class "Default")
      (node (ref "U28") (pin "55") (pinfunction "PB3_55") (pintype "unspecified"))
      (node (ref "U6") (pin "3") (pinfunction "3_3") (pintype "unspecified"))
    )
    (net (code "15") (name "ENC_SPI3_CS") (class "Default")
      (node (ref "U28") (pin "50") (pinfunction "PA15_50") (pintype "unspecified"))
      (node (ref "U48") (pin "2") (pinfunction "2_2") (pintype "unspecified"))
    )
    (net (code "16") (name "ENC_SPI3_MISO") (class "Default")
      (node (ref "U28") (pin "52") (pinfunction "PC11_52") (pintype "unspecified"))
      (node (ref "U48") (pin "4") (pinfunction "4_4") (pintype "unspecified"))
    )
    (net (code "17") (name "ENC_SPI3_MOSI") (class "Default")
      (node (ref "U28") (pin "53") (pinfunction "PC12_53") (pintype "unspecified"))
      (node (ref "U48") (pin "5") (pinfunction "5_5") (pintype "unspecified"))
    )
    (net (code "18") (name "ENC_SPI3_SCK") (class "Default")
      (node (ref "U28") (pin "51") (pinfunction "PC10_51") (pintype "unspecified"))
      (node (ref "U48") (pin "3") (pinfunction "3_3") (pintype "unspecified"))
    )
    (net (code "19") (name "GHA1") (class "Default")
      (node (ref "R1") (pin "2") (pinfunction "2_2") (pintype "unspecified"))
      (node (ref "U15") (pin "19") (pinfunction "HO1_19") (pintype "unspecified"))
    )
    (net (code "20") (name "GHA2") (class "Default")
      (node (ref "R40") (pin "2") (pinfunction "2_2") (pintype "unspecified"))
      (node (ref "U21") (pin "19") (pinfunction "HO1_19") (pintype "unspecified"))
    )
    (net (code "21") (name "GHB1") (class "Default")
      (node (ref "R12") (pin "2") (pinfunction "2_2") (pintype "unspecified"))
      (node (ref "U15") (pin "16") (pinfunction "HO2_16") (pintype "unspecified"))
    )
    (net (code "22") (name "GHB2") (class "Default")
      (node (ref "R42") (pin "2") (pinfunction "2_2") (pintype "unspecified"))
      (node (ref "U21") (pin "16") (pinfunction "HO2_16") (pintype "unspecified"))
    )
    (net (code "23") (name "GHC1") (class "Default")
      (node (ref "R27") (pin "2") (pinfunction "2_2") (pintype "unspecified"))
      (node (ref "U15") (pin "13") (pinfunction "HO3_13") (pintype "unspecified"))
    )
    (net (code "24") (name "GHC2") (class "Default")
      (node (ref "R44") (pin "2") (pinfunction "2_2") (pintype "unspecified"))
      (node (ref "U21") (pin "13") (pinfunction "HO3_13") (pintype "unspecified"))
    )
    (net (code "25") (name "GLA1") (class "Default")
      (node (ref "R2") (pin "2") (pinfunction "2_2") (pintype "unspecified"))
      (node (ref "U15") (pin "11") (pinfunction "LO1_11") (pintype "unspecified"))
    )
    (net (code "26") (name "GLA2") (class "Default")
      (node (ref "R41") (pin "2") (pinfunction "2_2") (pintype "unspecified"))
      (node (ref "U21") (pin "11") (pinfunction "LO1_11") (pintype "unspecified"))
    )
    (net (code "27") (name "GLB1") (class "Default")
      (node (ref "R13") (pin "2") (pinfunction "2_2") (pintype "unspecified"))
      (node (ref "U15") (pin "10") (pinfunction "LO2_10") (pintype "unspecified"))
    )
    (net (code "28") (name "GLB2") (class "Default")
      (node (ref "R43") (pin "2") (pinfunction "2_2") (pintype "unspecified"))
      (node (ref "U21") (pin "10") (pinfunction "LO2_10") (pintype "unspecified"))
    )
    (net (code "29") (name "GLC1") (class "Default")
      (node (ref "R28") (pin "2") (pinfunction "2_2") (pintype "unspecified"))
      (node (ref "U15") (pin "9") (pinfunction "LO3_9") (pintype "unspecified"))
    )
    (net (code "30") (name "GLC2") (class "Default")
      (node (ref "R45") (pin "2") (pinfunction "2_2") (pintype "unspecified"))
      (node (ref "U21") (pin "9") (pinfunction "LO3_9") (pintype "unspecified"))
    )
    (net (code "31") (name "IPS_CS") (class "Default")
      (node (ref "FPC1") (pin "1") (pinfunction "1_1") (pintype "unspecified"))
      (node (ref "U28") (pin "29") (pinfunction "PB10_29") (pintype "unspecified"))
    )
    (net (code "32") (name "IPS_DC") (class "Default")
      (node (ref "FPC1") (pin "5") (pinfunction "5_5") (pintype "unspecified"))
      (node (ref "U28") (pin "30") (pinfunction "PB11_30") (pintype "unspecified"))
    )
    (net (code "33") (name "IPS_MOSI") (class "Default")
      (node (ref "FPC1") (pin "4") (pinfunction "4_4") (pintype "unspecified"))
      (node (ref "U28") (pin "40") (pinfunction "PC9_40") (pintype "unspecified"))
    )
    (net (code "34") (name "IPS_RES") (class "Default")
      (node (ref "FPC1") (pin "6") (pinfunction "6_6") (pintype "unspecified"))
      (node (ref "U28") (pin "28") (pinfunction "PB2_28") (pintype "unspecified"))
    )
    (net (code "35") (name "IPS_SCK") (class "Default")
      (node (ref "FPC1") (pin "3") (pinfunction "3_3") (pintype "unspecified"))
      (node (ref "U28") (pin "33") (pinfunction "PB12_33") (pintype "unspecified"))
    )
    (net (code "36") (name "ISENSA1_PC1") (class "Default")
      (node (ref "R15") (pin "2") (pinfunction "2_2") (pintype "unspecified"))
      (node (ref "U1") (pin "7") (pinfunction "OUT2_7") (pintype "unspecified"))
      (node (ref "U28") (pin "9") (pinfunction "PC1_9") (pintype "unspecified"))
    )
    (net (code "37") (name "ISENSB1_PC0") (class "Default")
      (node (ref "R16") (pin "2") (pinfunction "2_2") (pintype "unspecified"))
      (node (ref "U1") (pin "1") (pinfunction "OUT1_1") (pintype "unspecified"))
      (node (ref "U28") (pin "8") (pinfunction "PC0_8") (pintype "unspecified"))
    )
    (net (code "38") (name "ISENSB2_PC2") (class "Default")
      (node (ref "R55") (pin "2") (pinfunction "2_2") (pintype "unspecified"))
      (node (ref "U20") (pin "1") (pinfunction "OUT1_1") (pintype "unspecified"))
      (node (ref "U28") (pin "10") (pinfunction "PC2_10") (pintype "unspecified"))
    )
    (net (code "39") (name "ISENSC2_PC3") (class "Default")
      (node (ref "R51") (pin "2") (pinfunction "2_2") (pintype "unspecified"))
      (node (ref "U20") (pin "7") (pinfunction "OUT2_7") (pintype "unspecified"))
      (node (ref "U28") (pin "11") (pinfunction "PC3_11") (pintype "unspecified"))
    )
    (net (code "40") (name "JTCK_SWCLK") (class "Default")
      (node (ref "H1") (pin "4") (pinfunction "4_4") (pintype "input"))
      (node (ref "U28") (pin "49") (pinfunction "PA14_49") (pintype "unspecified"))
    )
    (net (code "41") (name "JTMS_SWDIO") (class "Default")
      (node (ref "H1") (pin "2") (pinfunction "2_2") (pintype "input"))
      (node (ref "U28") (pin "46") (pinfunction "PA13_46") (pintype "unspecified"))
    )
    (net (code "42") (name "LED") (class "Default")
      (node (ref "R63") (pin "1") (pinfunction "1_1") (pintype "input"))
      (node (ref "U28") (pin "34") (pinfunction "PB13_34") (pintype "unspecified"))
    )
    (net (code "43") (name "M0_TEMP") (class "Default")
      (node (ref "C26") (pin "1") (pinfunction "1_1") (pintype "unspecified"))
      (node (ref "R8") (pin "2") (pinfunction "2_2") (pintype "unspecified"))
      (node (ref "RT1") (pin "1") (pinfunction "1_1") (pintype "unspecified"))
      (node (ref "U28") (pin "20") (pinfunction "PA4_20") (pintype "unspecified"))
    )
    (net (code "44") (name "Net-(LED3-A)") (class "Default")
      (node (ref "LED3") (pin "2") (pinfunction "A_2") (pintype "input"))
      (node (ref "R63") (pin "2") (pinfunction "2_2") (pintype "input"))
    )
    (net (code "45") (name "Net-(LED4-A)") (class "Default")
      (node (ref "LED4") (pin "2") (pinfunction "A_2") (pintype "input"))
      (node (ref "R64") (pin "2") (pinfunction "2_2") (pintype "input"))
    )
    (net (code "46") (name "Net-(LED5-A)") (class "Default")
      (node (ref "LED5") (pin "2") (pinfunction "A_2") (pintype "input"))
      (node (ref "R65") (pin "2") (pinfunction "2_2") (pintype "input"))
    )
    (net (code "47") (name "Net-(Q20-G)") (class "Default")
      (node (ref "Q20") (pin "1") (pinfunction "G_1") (pintype "unspecified"))
      (node (ref "R1") (pin "1") (pinfunction "1_1") (pintype "unspecified"))
    )
    (net (code "48") (name "Net-(Q21-G)") (class "Default")
      (node (ref "Q21") (pin "1") (pinfunction "G_1") (pintype "unspecified"))
      (node (ref "R2") (pin "1") (pinfunction "1_1") (pintype "unspecified"))
    )
    (net (code "49") (name "Net-(Q22-G)") (class "Default")
      (node (ref "Q22") (pin "1") (pinfunction "G_1") (pintype "unspecified"))
      (node (ref "R12") (pin "1") (pinfunction "1_1") (pintype "unspecified"))
    )
    (net (code "50") (name "Net-(Q23-G)") (class "Default")
      (node (ref "Q23") (pin "1") (pinfunction "G_1") (pintype "unspecified"))
      (node (ref "R13") (pin "1") (pinfunction "1_1") (pintype "unspecified"))
    )
    (net (code "51") (name "Net-(Q24-G)") (class "Default")
      (node (ref "Q24") (pin "1") (pinfunction "G_1") (pintype "unspecified"))
      (node (ref "R28") (pin "1") (pinfunction "1_1") (pintype "unspecified"))
    )
    (net (code "52") (name "Net-(Q25-G)") (class "Default")
      (node (ref "Q25") (pin "1") (pinfunction "G_1") (pintype "unspecified"))
      (node (ref "R27") (pin "1") (pinfunction "1_1") (pintype "unspecified"))
    )
    (net (code "53") (name "Net-(Q26-G)") (class "Default")
      (node (ref "Q26") (pin "1") (pinfunction "G_1") (pintype "unspecified"))
      (node (ref "R40") (pin "1") (pinfunction "1_1") (pintype "unspecified"))
    )
    (net (code "54") (name "Net-(Q27-G)") (class "Default")
      (node (ref "Q27") (pin "1") (pinfunction "G_1") (pintype "unspecified"))
      (node (ref "R41") (pin "1") (pinfunction "1_1") (pintype "unspecified"))
    )
    (net (code "55") (name "Net-(Q28-G)") (class "Default")
      (node (ref "Q28") (pin "1") (pinfunction "G_1") (pintype "unspecified"))
      (node (ref "R43") (pin "1") (pinfunction "1_1") (pintype "unspecified"))
    )
    (net (code "56") (name "Net-(Q29-G)") (class "Default")
      (node (ref "Q29") (pin "1") (pinfunction "G_1") (pintype "unspecified"))
      (node (ref "R42") (pin "1") (pinfunction "1_1") (pintype "unspecified"))
    )
    (net (code "57") (name "Net-(Q30-G)") (class "Default")
      (node (ref "Q30") (pin "1") (pinfunction "G_1") (pintype "unspecified"))
      (node (ref "R44") (pin "1") (pinfunction "1_1") (pintype "unspecified"))
    )
    (net (code "58") (name "Net-(Q31-G)") (class "Default")
      (node (ref "Q31") (pin "1") (pinfunction "G_1") (pintype "unspecified"))
      (node (ref "R45") (pin "1") (pinfunction "1_1") (pintype "unspecified"))
    )
    (net (code "59") (name "Net-(SW1-A)") (class "Default")
      (node (ref "C51") (pin "2") (pinfunction "2_2") (pintype "input"))
      (node (ref "SW1") (pin "1") (pinfunction "A_1") (pintype "unspecified"))
    )
    (net (code "60") (name "Net-(SW2-Pad3)") (class "Default")
      (node (ref "SW2") (pin "3") (pinfunction "3_3") (pintype "unspecified"))
      (node (ref "U35") (pin "1") (pinfunction "1_1") (pintype "unspecified"))
    )
    (net (code "61") (name "Net-(U1-1IN+)") (class "Default")
      (node (ref "R21") (pin "1") (pinfunction "1_1") (pintype "unspecified"))
      (node (ref "R22") (pin "1") (pinfunction "1_1") (pintype "unspecified"))
      (node (ref "U1") (pin "3") (pinfunction "1IN+_3") (pintype "unspecified"))
    )
    (net (code "62") (name "Net-(U1-1IN-)") (class "Default")
      (node (ref "R16") (pin "1") (pinfunction "1_1") (pintype "unspecified"))
      (node (ref "R19") (pin "1") (pinfunction "1_1") (pintype "unspecified"))
      (node (ref "U1") (pin "2") (pinfunction "1IN-_2") (pintype "unspecified"))
    )
    (net (code "63") (name "Net-(U1-2IN+)") (class "Default")
      (node (ref "R20") (pin "2") (pinfunction "2_2") (pintype "unspecified"))
      (node (ref "R26") (pin "2") (pinfunction "2_2") (pintype "unspecified"))
      (node (ref "U1") (pin "5") (pinfunction "2IN+_5") (pintype "unspecified"))
    )
    (net (code "64") (name "Net-(U1-2IN-)") (class "Default")
      (node (ref "R15") (pin "1") (pinfunction "1_1") (pintype "unspecified"))
      (node (ref "R23") (pin "2") (pinfunction "2_2") (pintype "unspecified"))
      (node (ref "U1") (pin "6") (pinfunction "2IN-_6") (pintype "unspecified"))
    )
    (net (code "65") (name "Net-(U13-BST)") (class "Default")
      (node (ref "C39") (pin "1") (pinfunction "1_1") (pintype "unspecified"))
      (node (ref "U13") (pin "1") (pinfunction "BST_1") (pintype "unspecified"))
    )
    (net (code "66") (name "Net-(U13-EN)") (class "Default")
      (node (ref "R31") (pin "1") (pinfunction "1_1") (pintype "unspecified"))
      (node (ref "U13") (pin "4") (pinfunction "EN_4") (pintype "unspecified"))
    )
    (net (code "67") (name "Net-(U13-FB)") (class "Default")
      (node (ref "R30") (pin "2") (pinfunction "2_2") (pintype "unspecified"))
      (node (ref "R59") (pin "1") (pinfunction "1_1") (pintype "unspecified"))
      (node (ref "U13") (pin "3") (pinfunction "FB_3") (pintype "unspecified"))
    )
    (net (code "68") (name "Net-(U13-SW)") (class "Default")
      (node (ref "C39") (pin "2") (pinfunction "2_2") (pintype "unspecified"))
      (node (ref "U13") (pin "6") (pinfunction "SW_6") (pintype "unspecified"))
      (node (ref "U25") (pin "1") (pinfunction "1_1") (pintype "unspecified"))
    )
    (net (code "69") (name "Net-(U20-1IN+)") (class "Default")
      (node (ref "R56") (pin "1") (pinfunction "1_1") (pintype "unspecified"))
      (node (ref "R58") (pin "1") (pinfunction "1_1") (pintype "unspecified"))
      (node (ref "U20") (pin "3") (pinfunction "1IN+_3") (pintype "unspecified"))
    )
    (net (code "70") (name "Net-(U20-1IN-)") (class "Default")
      (node (ref "R55") (pin "1") (pinfunction "1_1") (pintype "unspecified"))
      (node (ref "R57") (pin "1") (pinfunction "1_1") (pintype "unspecified"))
      (node (ref "U20") (pin "2") (pinfunction "1IN-_2") (pintype "unspecified"))
    )
    (net (code "71") (name "Net-(U20-2IN+)") (class "Default")
      (node (ref "R52") (pin "2") (pinfunction "2_2") (pintype "unspecified"))
      (node (ref "R53") (pin "2") (pinfunction "2_2") (pintype "unspecified"))
      (node (ref "U20") (pin "5") (pinfunction "2IN+_5") (pintype "unspecified"))
    )
    (net (code "72") (name "Net-(U20-2IN-)") (class "Default")
      (node (ref "R51") (pin "1") (pinfunction "1_1") (pintype "unspecified"))
      (node (ref "R54") (pin "2") (pinfunction "2_2") (pintype "unspecified"))
      (node (ref "U20") (pin "6") (pinfunction "2IN-_6") (pintype "unspecified"))
    )
    (net (code "73") (name "Net-(U28-BOOT0)") (class "Default")
      (node (ref "BOOT_RES") (pin "2") (pinfunction "2_2") (pintype "input"))
      (node (ref "R60") (pin "1") (pinfunction "1_1") (pintype "input"))
      (node (ref "U28") (pin "60") (pinfunction "BOOT0_60") (pintype "unspecified"))
    )
    (net (code "74") (name "Net-(U28-VCAP_1)") (class "Default")
      (node (ref "C50") (pin "2") (pinfunction "2_2") (pintype "input"))
      (node (ref "U28") (pin "31") (pinfunction "VCAP_1_31") (pintype "unspecified"))
    )
    (net (code "75") (name "Net-(U28-VCAP_2)") (class "Default")
      (node (ref "C48") (pin "1") (pinfunction "1_1") (pintype "input"))
      (node (ref "U28") (pin "47") (pinfunction "VCAP_2_47") (pintype "unspecified"))
    )
    (net (code "76") (name "Net-(U28-VDDA)") (class "Default")
      (node (ref "C46") (pin "1") (pinfunction "1_1") (pintype "input"))
      (node (ref "R62") (pin "2") (pinfunction "2_2") (pintype "input"))
      (node (ref "U28") (pin "13") (pinfunction "VDDA_13") (pintype "unspecified"))
    )
    (net (code "77") (name "Net-(U39-B)") (class "Default")
      (node (ref "Q28") (pin "2") (pinfunction "S_2") (pintype "unspecified"))
      (node (ref "Q28") (pin "3") (pinfunction "S_3") (pintype "unspecified"))
      (node (ref "Q28") (pin "4") (pinfunction "S_4") (pintype "unspecified"))
      (node (ref "Q28") (pin "5") (pinfunction "S_5") (pintype "unspecified"))
      (node (ref "Q28") (pin "6") (pinfunction "S_6") (pintype "unspecified"))
      (node (ref "R38") (pin "2") (pinfunction "2_2") (pintype "unspecified"))
      (node (ref "U39") (pin "2") (pinfunction "B_2") (pintype "input"))
    )
    (net (code "78") (name "Net-(U40-B)") (class "Default")
      (node (ref "Q31") (pin "2") (pinfunction "S_2") (pintype "unspecified"))
      (node (ref "Q31") (pin "3") (pinfunction "S_3") (pintype "unspecified"))
      (node (ref "Q31") (pin "4") (pinfunction "S_4") (pintype "unspecified"))
      (node (ref "Q31") (pin "5") (pinfunction "S_5") (pintype "unspecified"))
      (node (ref "Q31") (pin "6") (pinfunction "S_6") (pintype "unspecified"))
      (node (ref "R39") (pin "2") (pinfunction "2_2") (pintype "unspecified"))
      (node (ref "U40") (pin "2") (pinfunction "B_2") (pintype "input"))
    )
    (net (code "79") (name "Net-(U45-B)") (class "Default")
      (node (ref "Q23") (pin "2") (pinfunction "S_2") (pintype "unspecified"))
      (node (ref "Q23") (pin "3") (pinfunction "S_3") (pintype "unspecified"))
      (node (ref "Q23") (pin "4") (pinfunction "S_4") (pintype "unspecified"))
      (node (ref "Q23") (pin "5") (pinfunction "S_5") (pintype "unspecified"))
      (node (ref "Q23") (pin "6") (pinfunction "S_6") (pintype "unspecified"))
      (node (ref "R4") (pin "2") (pinfunction "2_2") (pintype "unspecified"))
      (node (ref "U45") (pin "2") (pinfunction "B_2") (pintype "input"))
    )
    (net (code "80") (name "Net-(U46-B)") (class "Default")
      (node (ref "Q21") (pin "2") (pinfunction "S_2") (pintype "unspecified"))
      (node (ref "Q21") (pin "3") (pinfunction "S_3") (pintype "unspecified"))
      (node (ref "Q21") (pin "4") (pinfunction "S_4") (pintype "unspecified"))
      (node (ref "Q21") (pin "5") (pinfunction "S_5") (pintype "unspecified"))
      (node (ref "Q21") (pin "6") (pinfunction "S_6") (pintype "unspecified"))
      (node (ref "R29") (pin "2") (pinfunction "2_2") (pintype "unspecified"))
      (node (ref "U46") (pin "2") (pinfunction "B_2") (pintype "input"))
    )
    (net (code "81") (name "OS_8M_IN") (class "Default")
      (node (ref "C52") (pin "1") (pinfunction "1_1") (pintype "input"))
      (node (ref "U28") (pin "5") (pinfunction "PH0_5") (pintype "unspecified"))
      (node (ref "X1") (pin "1") (pinfunction "1_1") (pintype "input"))
    )
    (net (code "82") (name "OS_8M_OUT") (class "Default")
      (node (ref "C53") (pin "2") (pinfunction "2_2") (pintype "input"))
      (node (ref "U28") (pin "6") (pinfunction "PH1_6") (pintype "unspecified"))
      (node (ref "X1") (pin "3") (pinfunction "3_3") (pintype "input"))
    )
    (net (code "83") (name "PGND") (class "Default")
      (node (ref "C13") (pin "1") (pinfunction "1_1") (pintype "unspecified"))
      (node (ref "C14") (pin "1") (pinfunction "1_1") (pintype "unspecified"))
      (node (ref "C19") (pin "1") (pinfunction "1_1") (pintype "unspecified"))
      (node (ref "C22") (pin "1") (pinfunction "1_1") (pintype "unspecified"))
      (node (ref "C23") (pin "1") (pinfunction "1_1") (pintype "unspecified"))
      (node (ref "C24") (pin "1") (pinfunction "1_1") (pintype "unspecified"))
      (node (ref "C25") (pin "1") (pinfunction "1_1") (pintype "unspecified"))
      (node (ref "C28") (pin "1") (pinfunction "1_1") (pintype "unspecified"))
      (node (ref "C36") (pin "1") (pinfunction "1_1") (pintype "unspecified"))
      (node (ref "C6") (pin "1") (pinfunction "1_1") (pintype "unspecified"))
      (node (ref "Q24") (pin "2") (pinfunction "S_2") (pintype "unspecified"))
      (node (ref "Q24") (pin "3") (pinfunction "S_3") (pintype "unspecified"))
      (node (ref "Q24") (pin "4") (pinfunction "S_4") (pintype "unspecified"))
      (node (ref "Q24") (pin "5") (pinfunction "S_5") (pintype "unspecified"))
      (node (ref "Q24") (pin "6") (pinfunction "S_6") (pintype "unspecified"))
      (node (ref "Q27") (pin "2") (pinfunction "S_2") (pintype "unspecified"))
      (node (ref "Q27") (pin "3") (pinfunction "S_3") (pintype "unspecified"))
      (node (ref "Q27") (pin "4") (pinfunction "S_4") (pintype "unspecified"))
      (node (ref "Q27") (pin "5") (pinfunction "S_5") (pintype "unspecified"))
      (node (ref "Q27") (pin "6") (pinfunction "S_6") (pintype "unspecified"))
      (node (ref "R18") (pin "1") (pinfunction "1_1") (pintype "unspecified"))
      (node (ref "R29") (pin "1") (pinfunction "1_1") (pintype "unspecified"))
      (node (ref "R38") (pin "1") (pinfunction "1_1") (pintype "unspecified"))
      (node (ref "R39") (pin "1") (pinfunction "1_1") (pintype "unspecified"))
      (node (ref "R4") (pin "1") (pinfunction "1_1") (pintype "unspecified"))
      (node (ref "U35") (pin "2") (pinfunction "2_2") (pintype "unspecified"))
      (node (ref "U38") (pin "2") (pinfunction "B_2") (pintype "input"))
      (node (ref "U41") (pin "2") (pinfunction "B_2") (pintype "input"))
      (node (ref "U44") (pin "2") (pinfunction "B_2") (pintype "input"))
      (node (ref "U47") (pin "2") (pinfunction "B_2") (pintype "input"))
    )
    (net (code "84") (name "PWM_TIM1_CH1N_PA7_INLA1") (class "Default")
      (node (ref "U15") (pin "1") (pinfunction "LIN1_1") (pintype "unspecified"))
      (node (ref "U28") (pin "23") (pinfunction "PA7_23") (pintype "unspecified"))
    )
    (net (code "85") (name "PWM_TIM1_CH1_PA8_INHA1") (class "Default")
      (node (ref "U15") (pin "22") (pinfunction "HIN1_22") (pintype "unspecified"))
      (node (ref "U28") (pin "41") (pinfunction "PA8_41") (pintype "unspecified"))
    )
    (net (code "86") (name "PWM_TIM1_CH2N_PB0_INLB1") (class "Default")
      (node (ref "U15") (pin "2") (pinfunction "LIN2_2") (pintype "unspecified"))
      (node (ref "U28") (pin "26") (pinfunction "PB0_26") (pintype "unspecified"))
    )
    (net (code "87") (name "PWM_TIM1_CH2_PA9_INHB1") (class "Default")
      (node (ref "U15") (pin "23") (pinfunction "HIN2_23") (pintype "unspecified"))
      (node (ref "U28") (pin "42") (pinfunction "PA9_42") (pintype "unspecified"))
    )
    (net (code "88") (name "PWM_TIM1_CH3N_PB1_INLC1") (class "Default")
      (node (ref "U15") (pin "3") (pinfunction "LIN3_3") (pintype "unspecified"))
      (node (ref "U28") (pin "27") (pinfunction "PB1_27") (pintype "unspecified"))
    )
    (net (code "89") (name "PWM_TIM1_CH3_PA10_INHC1") (class "Default")
      (node (ref "U15") (pin "24") (pinfunction "HIN3_24") (pintype "unspecified"))
      (node (ref "U28") (pin "43") (pinfunction "PA10_43") (pintype "unspecified"))
    )
    (net (code "90") (name "PWM_TIM8_CH1N_PA5_INLA2") (class "Default")
      (node (ref "U21") (pin "1") (pinfunction "LIN1_1") (pintype "unspecified"))
      (node (ref "U28") (pin "21") (pinfunction "PA5_21") (pintype "unspecified"))
    )
    (net (code "91") (name "PWM_TIM8_CH1_PC6_INHA2") (class "Default")
      (node (ref "U21") (pin "22") (pinfunction "HIN1_22") (pintype "unspecified"))
      (node (ref "U28") (pin "37") (pinfunction "PC6_37") (pintype "unspecified"))
    )
    (net (code "92") (name "PWM_TIM8_CH2N_PB14_INLB2") (class "Default")
      (node (ref "U21") (pin "2") (pinfunction "LIN2_2") (pintype "unspecified"))
      (node (ref "U28") (pin "35") (pinfunction "PB14_35") (pintype "unspecified"))
    )
    (net (code "93") (name "PWM_TIM8_CH2_PC7_INHB2") (class "Default")
      (node (ref "U21") (pin "23") (pinfunction "HIN2_23") (pintype "unspecified"))
      (node (ref "U28") (pin "38") (pinfunction "PC7_38") (pintype "unspecified"))
    )
    (net (code "94") (name "PWM_TIM8_CH3N_PB15_INLC2") (class "Default")
      (node (ref "U21") (pin "3") (pinfunction "LIN3_3") (pintype "unspecified"))
      (node (ref "U28") (pin "36") (pinfunction "PB15_36") (pintype "unspecified"))
    )
    (net (code "95") (name "PWM_TIM8_CH3_PC8_INHC2") (class "Default")
      (node (ref "U21") (pin "24") (pinfunction "HIN3_24") (pintype "unspecified"))
      (node (ref "U28") (pin "39") (pinfunction "PC8_39") (pintype "unspecified"))
    )
    (net (code "96") (name "RST") (class "Default")
      (node (ref "C51") (pin "1") (pinfunction "1_1") (pintype "input"))
      (node (ref "H1") (pin "10") (pinfunction "10_10") (pintype "input"))
      (node (ref "R61") (pin "2") (pinfunction "2_2") (pintype "input"))
      (node (ref "SW1") (pin "3") (pinfunction "C_3") (pintype "unspecified"))
      (node (ref "U28") (pin "7") (pinfunction "NRST_7") (pintype "unspecified"))
    )
    (net (code "97") (name "SHA1") (class "Default")
      (node (ref "C27") (pin "1") (pinfunction "1_1") (pintype "unspecified"))
      (node (ref "Q20") (pin "2") (pinfunction "S_2") (pintype "unspecified"))
      (node (ref "Q20") (pin "3") (pinfunction "S_3") (pintype "unspecified"))
      (node (ref "Q20") (pin "4") (pinfunction "S_4") (pintype "unspecified"))
      (node (ref "Q20") (pin "5") (pinfunction "S_5") (pintype "unspecified"))
      (node (ref "Q20") (pin "6") (pinfunction "S_6") (pintype "unspecified"))
      (node (ref "Q21") (pin "10") (pinfunction "D_10") (pintype "unspecified"))
      (node (ref "Q21") (pin "7") (pinfunction "D_7") (pintype "unspecified"))
      (node (ref "Q21") (pin "8") (pinfunction "D_8") (pintype "unspecified"))
      (node (ref "Q21") (pin "9") (pinfunction "D_9") (pintype "unspecified"))
      (node (ref "U15") (pin "18") (pinfunction "VS1_18") (pintype "unspecified"))
      (node (ref "XT2") (pin "1") (pinfunction "1_1") (pintype "unspecified"))
    )
    (net (code "98") (name "SHA2") (class "Default")
      (node (ref "C35") (pin "1") (pinfunction "1_1") (pintype "unspecified"))
      (node (ref "Q26") (pin "2") (pinfunction "S_2") (pintype "unspecified"))
      (node (ref "Q26") (pin "3") (pinfunction "S_3") (pintype "unspecified"))
      (node (ref "Q26") (pin "4") (pinfunction "S_4") (pintype "unspecified"))
      (node (ref "Q26") (pin "5") (pinfunction "S_5") (pintype "unspecified"))
      (node (ref "Q26") (pin "6") (pinfunction "S_6") (pintype "unspecified"))
      (node (ref "Q27") (pin "10") (pinfunction "D_10") (pintype "unspecified"))
      (node (ref "Q27") (pin "7") (pinfunction "D_7") (pintype "unspecified"))
      (node (ref "Q27") (pin "8") (pinfunction "D_8") (pintype "unspecified"))
      (node (ref "Q27") (pin "9") (pinfunction "D_9") (pintype "unspecified"))
      (node (ref "U21") (pin "18") (pinfunction "VS1_18") (pintype "unspecified"))
      (node (ref "XT1") (pin "1") (pinfunction "1_1") (pintype "unspecified"))
    )
    (net (code "99") (name "SHB1") (class "Default")
      (node (ref "C1") (pin "1") (pinfunction "1_1") (pintype "unspecified"))
      (node (ref "Q22") (pin "2") (pinfunction "S_2") (pintype "unspecified"))
      (node (ref "Q22") (pin "3") (pinfunction "S_3") (pintype "unspecified"))
      (node (ref "Q22") (pin "4") (pinfunction "S_4") (pintype "unspecified"))
      (node (ref "Q22") (pin "5") (pinfunction "S_5") (pintype "unspecified"))
      (node (ref "Q22") (pin "6") (pinfunction "S_6") (pintype "unspecified"))
      (node (ref "Q23") (pin "10") (pinfunction "D_10") (pintype "unspecified"))
      (node (ref "Q23") (pin "7") (pinfunction "D_7") (pintype "unspecified"))
      (node (ref "Q23") (pin "8") (pinfunction "D_8") (pintype "unspecified"))
      (node (ref "Q23") (pin "9") (pinfunction "D_9") (pintype "unspecified"))
      (node (ref "U15") (pin "15") (pinfunction "VS2_15") (pintype "unspecified"))
      (node (ref "XT2") (pin "2") (pinfunction "2_2") (pintype "unspecified"))
    )
    (net (code "100") (name "SHB2") (class "Default")
      (node (ref "C33") (pin "1") (pinfunction "1_1") (pintype "unspecified"))
      (node (ref "Q28") (pin "10") (pinfunction "D_10") (pintype "unspecified"))
      (node (ref "Q28") (pin "7") (pinfunction "D_7") (pintype "unspecified"))
      (node (ref "Q28") (pin "8") (pinfunction "D_8") (pintype "unspecified"))
      (node (ref "Q28") (pin "9") (pinfunction "D_9") (pintype "unspecified"))
      (node (ref "Q29") (pin "2") (pinfunction "S_2") (pintype "unspecified"))
      (node (ref "Q29") (pin "3") (pinfunction "S_3") (pintype "unspecified"))
      (node (ref "Q29") (pin "4") (pinfunction "S_4") (pintype "unspecified"))
      (node (ref "Q29") (pin "5") (pinfunction "S_5") (pintype "unspecified"))
      (node (ref "Q29") (pin "6") (pinfunction "S_6") (pintype "unspecified"))
      (node (ref "U21") (pin "15") (pinfunction "VS2_15") (pintype "unspecified"))
      (node (ref "XT1") (pin "2") (pinfunction "2_2") (pintype "unspecified"))
    )
    (net (code "101") (name "SHC1") (class "Default")
      (node (ref "C18") (pin "1") (pinfunction "1_1") (pintype "unspecified"))
      (node (ref "Q24") (pin "10") (pinfunction "D_10") (pintype "unspecified"))
      (node (ref "Q24") (pin "7") (pinfunction "D_7") (pintype "unspecified"))
      (node (ref "Q24") (pin "8") (pinfunction "D_8") (pintype "unspecified"))
      (node (ref "Q24") (pin "9") (pinfunction "D_9") (pintype "unspecified"))
      (node (ref "Q25") (pin "2") (pinfunction "S_2") (pintype "unspecified"))
      (node (ref "Q25") (pin "3") (pinfunction "S_3") (pintype "unspecified"))
      (node (ref "Q25") (pin "4") (pinfunction "S_4") (pintype "unspecified"))
      (node (ref "Q25") (pin "5") (pinfunction "S_5") (pintype "unspecified"))
      (node (ref "Q25") (pin "6") (pinfunction "S_6") (pintype "unspecified"))
      (node (ref "U15") (pin "12") (pinfunction "VS3_12") (pintype "unspecified"))
      (node (ref "XT2") (pin "3") (pinfunction "3_3") (pintype "unspecified"))
    )
    (net (code "102") (name "SHC2") (class "Default")
      (node (ref "C34") (pin "1") (pinfunction "1_1") (pintype "unspecified"))
      (node (ref "Q30") (pin "2") (pinfunction "S_2") (pintype "unspecified"))
      (node (ref "Q30") (pin "3") (pinfunction "S_3") (pintype "unspecified"))
      (node (ref "Q30") (pin "4") (pinfunction "S_4") (pintype "unspecified"))
      (node (ref "Q30") (pin "5") (pinfunction "S_5") (pintype "unspecified"))
      (node (ref "Q30") (pin "6") (pinfunction "S_6") (pintype "unspecified"))
      (node (ref "Q31") (pin "10") (pinfunction "D_10") (pintype "unspecified"))
      (node (ref "Q31") (pin "7") (pinfunction "D_7") (pintype "unspecified"))
      (node (ref "Q31") (pin "8") (pinfunction "D_8") (pintype "unspecified"))
      (node (ref "Q31") (pin "9") (pinfunction "D_9") (pintype "unspecified"))
      (node (ref "U21") (pin "12") (pinfunction "VS3_12") (pintype "unspecified"))
      (node (ref "XT1") (pin "3") (pinfunction "3_3") (pintype "unspecified"))
    )
    (net (code "103") (name "SNA1") (class "Default")
      (node (ref "R23") (pin "1") (pinfunction "1_1") (pintype "unspecified"))
      (node (ref "U47") (pin "1") (pinfunction "A_1") (pintype "input"))
    )
    (net (code "104") (name "SNB1") (class "Default")
      (node (ref "R19") (pin "2") (pinfunction "2_2") (pintype "unspecified"))
      (node (ref "U44") (pin "1") (pinfunction "A_1") (pintype "input"))
    )
    (net (code "105") (name "SNB2") (class "Default")
      (node (ref "R57") (pin "2") (pinfunction "2_2") (pintype "unspecified"))
      (node (ref "U38") (pin "1") (pinfunction "A_1") (pintype "input"))
    )
    (net (code "106") (name "SNC2") (class "Default")
      (node (ref "R54") (pin "1") (pinfunction "1_1") (pintype "unspecified"))
      (node (ref "U41") (pin "1") (pinfunction "A_1") (pintype "input"))
    )
    (net (code "107") (name "SPA1") (class "Default")
      (node (ref "R26") (pin "1") (pinfunction "1_1") (pintype "unspecified"))
      (node (ref "U46") (pin "1") (pinfunction "A_1") (pintype "input"))
    )
    (net (code "108") (name "SPB1") (class "Default")
      (node (ref "R21") (pin "2") (pinfunction "2_2") (pintype "unspecified"))
      (node (ref "U45") (pin "1") (pinfunction "A_1") (pintype "input"))
    )
    (net (code "109") (name "SPB2") (class "Default")
      (node (ref "R58") (pin "2") (pinfunction "2_2") (pintype "unspecified"))
      (node (ref "U39") (pin "1") (pinfunction "A_1") (pintype "input"))
    )
    (net (code "110") (name "SPC2") (class "Default")
      (node (ref "R53") (pin "1") (pinfunction "1_1") (pintype "unspecified"))
      (node (ref "U40") (pin "1") (pinfunction "A_1") (pintype "input"))
    )
    (net (code "111") (name "USART1_RX") (class "Default")
      (node (ref "H1") (pin "9") (pinfunction "9_9") (pintype "input"))
      (node (ref "U28") (pin "58") (pinfunction "PB6_58") (pintype "unspecified"))
    )
    (net (code "112") (name "USART1_TX") (class "Default")
      (node (ref "H1") (pin "7") (pinfunction "7_7") (pintype "input"))
      (node (ref "U28") (pin "59") (pinfunction "PB7_59") (pintype "unspecified"))
    )
    (net (code "113") (name "USART2_RX") (class "Default")
      (node (ref "U28") (pin "17") (pinfunction "PA3_17") (pintype "unspecified"))
    )
    (net (code "114") (name "USART2_TX") (class "Default")
      (node (ref "U28") (pin "16") (pinfunction "PA2_16") (pintype "unspecified"))
    )
    (net (code "115") (name "VBA1") (class "Default")
      (node (ref "C27") (pin "2") (pinfunction "2_2") (pintype "unspecified"))
      (node (ref "U15") (pin "20") (pinfunction "VB1_20") (pintype "unspecified"))
      (node (ref "U17") (pin "1") (pinfunction "C_1") (pintype "unspecified"))
    )
    (net (code "116") (name "VBA2") (class "Default")
      (node (ref "C35") (pin "2") (pinfunction "2_2") (pintype "unspecified"))
      (node (ref "U21") (pin "20") (pinfunction "VB1_20") (pintype "unspecified"))
      (node (ref "U23") (pin "1") (pinfunction "C_1") (pintype "unspecified"))
    )
    (net (code "117") (name "VBB1") (class "Default")
      (node (ref "C1") (pin "2") (pinfunction "2_2") (pintype "unspecified"))
      (node (ref "U15") (pin "17") (pinfunction "VB2_17") (pintype "unspecified"))
      (node (ref "U18") (pin "1") (pinfunction "C_1") (pintype "unspecified"))
    )
    (net (code "118") (name "VBB2") (class "Default")
      (node (ref "C33") (pin "2") (pinfunction "2_2") (pintype "unspecified"))
      (node (ref "U21") (pin "17") (pinfunction "VB2_17") (pintype "unspecified"))
      (node (ref "U24") (pin "1") (pinfunction "C_1") (pintype "unspecified"))
    )
    (net (code "119") (name "VBC1") (class "Default")
      (node (ref "C18") (pin "2") (pinfunction "2_2") (pintype "unspecified"))
      (node (ref "U15") (pin "14") (pinfunction "VB3_14") (pintype "unspecified"))
      (node (ref "U16") (pin "1") (pinfunction "C_1") (pintype "unspecified"))
    )
    (net (code "120") (name "VBC2") (class "Default")
      (node (ref "C34") (pin "2") (pinfunction "2_2") (pintype "unspecified"))
      (node (ref "U21") (pin "14") (pinfunction "VB3_14") (pintype "unspecified"))
      (node (ref "U22") (pin "1") (pinfunction "C_1") (pintype "unspecified"))
    )
    (net (code "121") (name "VBUS_S_PA1") (class "Default")
      (node (ref "C16") (pin "2") (pinfunction "2_2") (pintype "unspecified"))
      (node (ref "R11") (pin "2") (pinfunction "2_2") (pintype "unspecified"))
      (node (ref "R24") (pin "1") (pinfunction "1_1") (pintype "unspecified"))
      (node (ref "U28") (pin "15") (pinfunction "PA1_15") (pintype "unspecified"))
    )
    (net (code "122") (name "VCC") (class "Default")
      (node (ref "BOOT_RES") (pin "1") (pinfunction "1_1") (pintype "input"))
      (node (ref "C29") (pin "1") (pinfunction "1_1") (pintype "unspecified"))
      (node (ref "C31") (pin "1") (pinfunction "1_1") (pintype "unspecified"))
      (node (ref "C42") (pin "2") (pinfunction "2_2") (pintype "unspecified"))
      (node (ref "C43") (pin "2") (pinfunction "2_2") (pintype "unspecified"))
      (node (ref "C44") (pin "1") (pinfunction "1_1") (pintype "input"))
      (node (ref "C45") (pin "1") (pinfunction "1_1") (pintype "input"))
      (node (ref "C47") (pin "1") (pinfunction "1_1") (pintype "input"))
      (node (ref "C49") (pin "2") (pinfunction "2_2") (pintype "input"))
      (node (ref "C5") (pin "1") (pinfunction "1_1") (pintype "unspecified"))
      (node (ref "C54") (pin "2") (pinfunction "2_2") (pintype "input"))
      (node (ref "FPC1") (pin "2") (pinfunction "2_2") (pintype "unspecified"))
      (node (ref "FPC1") (pin "8") (pinfunction "8_8") (pintype "unspecified"))
      (node (ref "H1") (pin "1") (pinfunction "1_1") (pintype "input"))
      (node (ref "R20") (pin "1") (pinfunction "1_1") (pintype "unspecified"))
      (node (ref "R22") (pin "2") (pinfunction "2_2") (pintype "unspecified"))
      (node (ref "R52") (pin "1") (pinfunction "1_1") (pintype "unspecified"))
      (node (ref "R56") (pin "2") (pinfunction "2_2") (pintype "unspecified"))
      (node (ref "R61") (pin "1") (pinfunction "1_1") (pintype "input"))
      (node (ref "R62") (pin "1") (pinfunction "1_1") (pintype "input"))
      (node (ref "R64") (pin "1") (pinfunction "1_1") (pintype "input"))
      (node (ref "RT1") (pin "2") (pinfunction "2_2") (pintype "unspecified"))
      (node (ref "U1") (pin "8") (pinfunction "VCC_8") (pintype "unspecified"))
      (node (ref "U14") (pin "5") (pinfunction "OUT_5") (pintype "unspecified"))
      (node (ref "U20") (pin "8") (pinfunction "VCC_8") (pintype "unspecified"))
      (node (ref "U28") (pin "1") (pinfunction "VBAT_1") (pintype "unspecified"))
      (node (ref "U28") (pin "19") (pinfunction "VDD_19") (pintype "unspecified"))
      (node (ref "U28") (pin "32") (pinfunction "VDD_32") (pintype "unspecified"))
      (node (ref "U28") (pin "48") (pinfunction "VDD_48") (pintype "unspecified"))
      (node (ref "U28") (pin "64") (pinfunction "VDD_64") (pintype "unspecified"))
      (node (ref "U4") (pin "3") (pinfunction "VCC_3") (pintype "unspecified"))
      (node (ref "U48") (pin "6") (pinfunction "6_6") (pintype "unspecified"))
      (node (ref "U6") (pin "6") (pinfunction "6_6") (pintype "unspecified"))
    )
    (net (code "123") (name "unconnected-(H1-Pad6)") (class "Default")
      (node (ref "H1") (pin "6") (pinfunction "6_6") (pintype "input"))
    )
    (net (code "124") (name "unconnected-(H1-Pad8)") (class "Default")
      (node (ref "H1") (pin "8") (pinfunction "8_8") (pintype "input"))
    )
    (net (code "125") (name "unconnected-(SW1-B-Pad2)") (class "Default")
      (node (ref "SW1") (pin "2") (pinfunction "B_2") (pintype "unspecified+no_connect"))
    )
    (net (code "126") (name "unconnected-(SW1-D-Pad4)") (class "Default")
      (node (ref "SW1") (pin "4") (pinfunction "D_4") (pintype "unspecified+no_connect"))
    )
    (net (code "127") (name "unconnected-(U4-SHDN-Pad5)") (class "Default")
      (node (ref "U4") (pin "5") (pinfunction "SHDN_5") (pintype "unspecified+no_connect"))
    )
    (net (code "128") (name "unconnected-(U14-BYP-Pad4)") (class "Default")
      (node (ref "U14") (pin "4") (pinfunction "BYP_4") (pintype "unspecified+no_connect"))
    )
    (net (code "129") (name "unconnected-(U15-EP-Pad25)") (class "Default")
      (node (ref "U15") (pin "25") (pinfunction "EP_25") (pintype "unspecified"))
    )
    (net (code "130") (name "unconnected-(U15-NC-Pad5)") (class "Default")
      (node (ref "U15") (pin "5") (pinfunction "NC_5") (pintype "unspecified+no_connect"))
    )
    (net (code "131") (name "unconnected-(U15-NC-Pad7)") (class "Default")
      (node (ref "U15") (pin "7") (pinfunction "NC_7") (pintype "unspecified+no_connect"))
    )
    (net (code "132") (name "unconnected-(U15-NC-Pad8)") (class "Default")
      (node (ref "U15") (pin "8") (pinfunction "NC_8") (pintype "unspecified+no_connect"))
    )
    (net (code "133") (name "unconnected-(U15-NC-Pad21)") (class "Default")
      (node (ref "U15") (pin "21") (pinfunction "NC_21") (pintype "unspecified+no_connect"))
    )
    (net (code "134") (name "unconnected-(U21-EP-Pad25)") (class "Default")
      (node (ref "U21") (pin "25") (pinfunction "EP_25") (pintype "unspecified"))
    )
    (net (code "135") (name "unconnected-(U21-NC-Pad5)") (class "Default")
      (node (ref "U21") (pin "5") (pinfunction "NC_5") (pintype "unspecified+no_connect"))
    )
    (net (code "136") (name "unconnected-(U21-NC-Pad7)") (class "Default")
      (node (ref "U21") (pin "7") (pinfunction "NC_7") (pintype "unspecified+no_connect"))
    )
    (net (code "137") (name "unconnected-(U21-NC-Pad8)") (class "Default")
      (node (ref "U21") (pin "8") (pinfunction "NC_8") (pintype "unspecified+no_connect"))
    )
    (net (code "138") (name "unconnected-(U21-NC-Pad21)") (class "Default")
      (node (ref "U21") (pin "21") (pinfunction "NC_21") (pintype "unspecified+no_connect"))
    )
    (net (code "139") (name "unconnected-(U28-PA0_WKUP-Pad14)") (class "Default")
      (node (ref "U28") (pin "14") (pinfunction "PA0_WKUP_14") (pintype "unspecified"))
    )
    (net (code "140") (name "unconnected-(U28-PA6-Pad22)") (class "Default")
      (node (ref "U28") (pin "22") (pinfunction "PA6_22") (pintype "unspecified"))
    )
    (net (code "141") (name "unconnected-(U28-PA11-Pad44)") (class "Default")
      (node (ref "U28") (pin "44") (pinfunction "PA11_44") (pintype "unspecified"))
    )
    (net (code "142") (name "unconnected-(U28-PA12-Pad45)") (class "Default")
      (node (ref "U28") (pin "45") (pinfunction "PA12_45") (pintype "unspecified"))
    )
    (net (code "143") (name "unconnected-(U28-PC13-Pad2)") (class "Default")
      (node (ref "U28") (pin "2") (pinfunction "PC13_2") (pintype "unspecified"))
    )
    (net (code "144") (name "unconnected-(U28-PC14-Pad3)") (class "Default")
      (node (ref "U28") (pin "3") (pinfunction "PC14_3") (pintype "unspecified"))
    )
    (net (code "145") (name "unconnected-(U28-PC15-Pad4)") (class "Default")
      (node (ref "U28") (pin "4") (pinfunction "PC15_4") (pintype "unspecified"))
    )
  )
)
